# Sheet1.net
KiCad netlist of a schematic drawn in Altium Designer
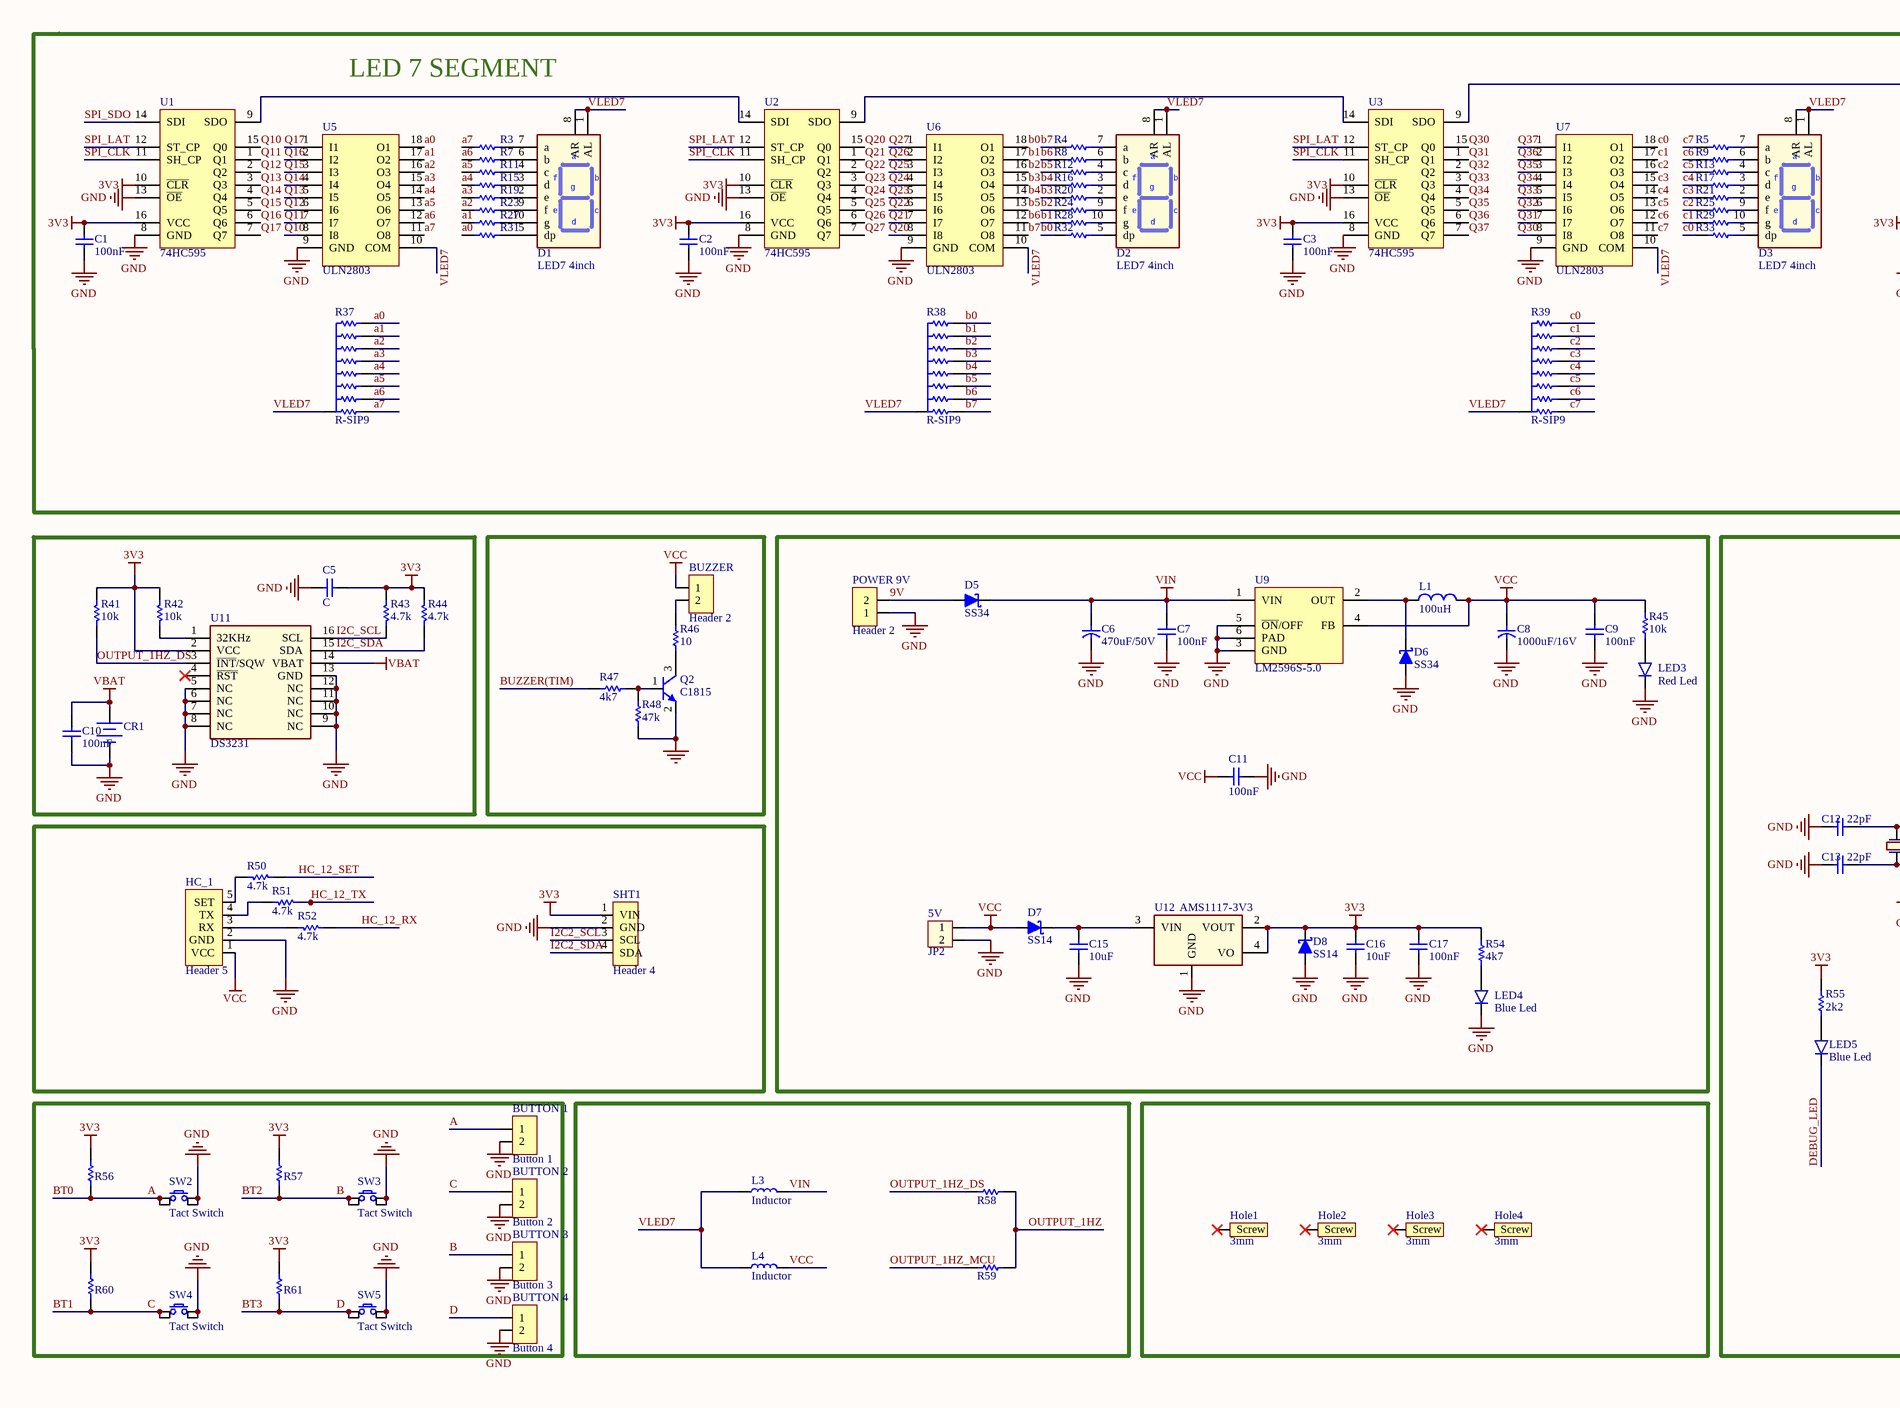
[diagram p0: Sheet1.SchDoc, left]
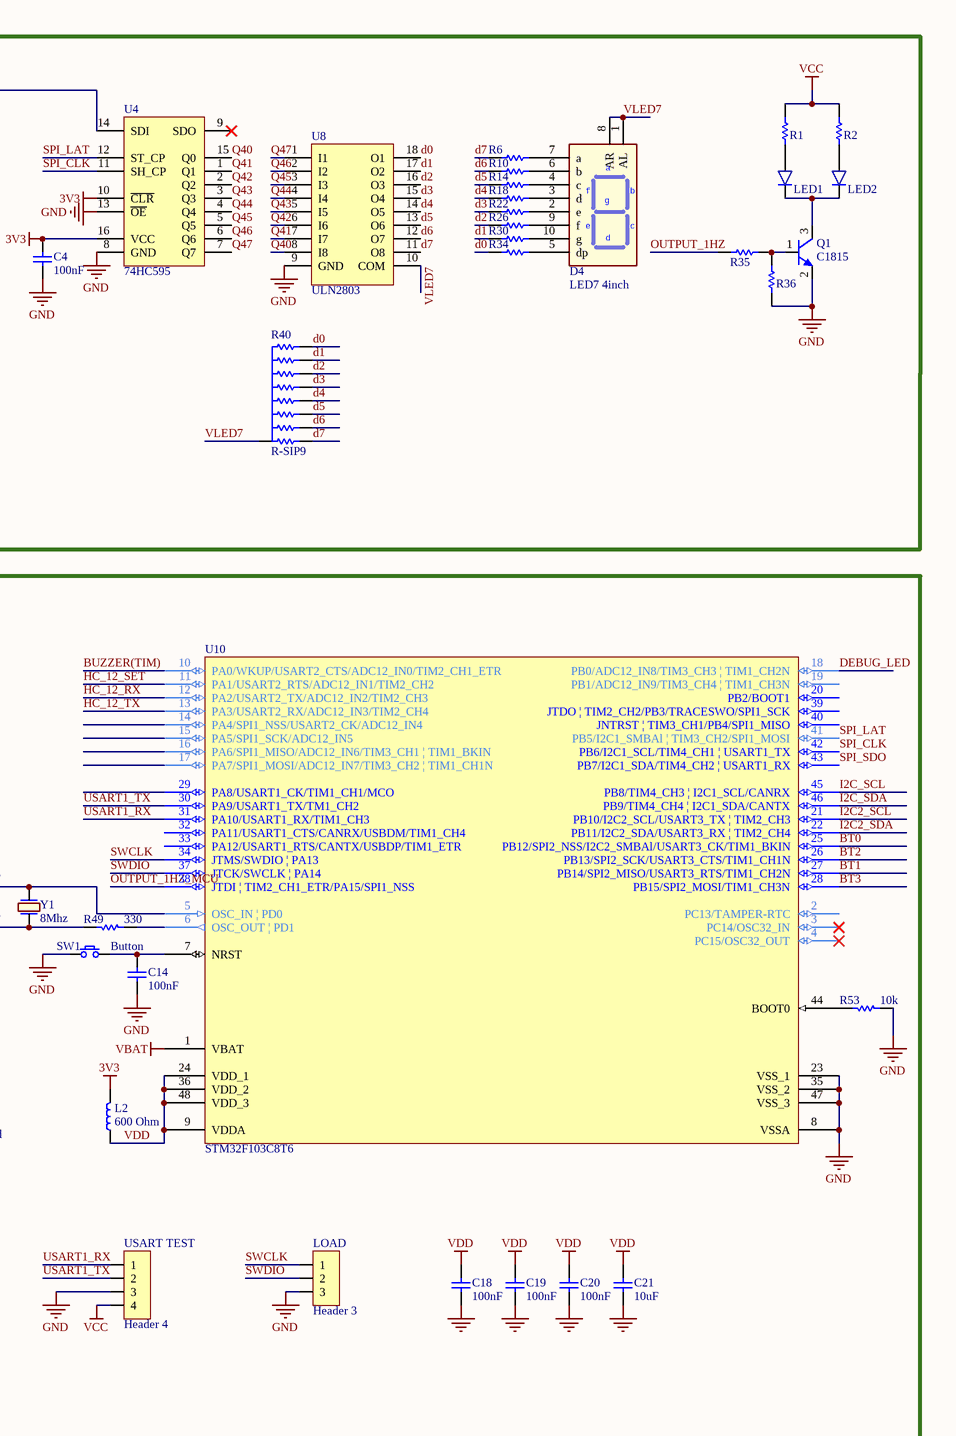
[diagram p1: Sheet1.SchDoc, right]

(export (version "E")
  (design (tool "Eeschema 10.0.6"))
  (components
    (comp (ref "5V")
      (value "JP2")
      (footprint "CON Header 2")
      (description "Connector 2")
      (libsource (lib "BKIT4U_LIB") (part "Con2"))
    )
    (comp (ref "BUTTON 1")
      (value "Button 1")
      (footprint "CON Header 2")
      (description "Header, 2-Pin")
      (fields (field (name "PUBLISHER") "Altium Limited"))
      (libsource (lib "BKIT4U_LIB") (part "Header 2"))
    )
    (comp (ref "BUTTON 2")
      (value "Button 2")
      (footprint "CON Header 2")
      (description "Header, 2-Pin")
      (fields (field (name "PUBLISHER") "Altium Limited"))
      (libsource (lib "BKIT4U_LIB") (part "Header 2"))
    )
    (comp (ref "BUTTON 3")
      (value "Button 3")
      (footprint "CON Header 2")
      (description "Header, 2-Pin")
      (fields (field (name "PUBLISHER") "Altium Limited"))
      (libsource (lib "BKIT4U_LIB") (part "Header 2"))
    )
    (comp (ref "BUTTON 4")
      (value "Button 4")
      (footprint "CON Header 2")
      (description "Header, 2-Pin")
      (fields (field (name "PUBLISHER") "Altium Limited"))
      (libsource (lib "BKIT4U_LIB") (part "Header 2"))
    )
    (comp (ref "BUZZER")
      (value "Header 2")
      (footprint "CON Header 2")
      (description "Header, 2-Pin")
      (fields (field (name "PUBLISHER") "Altium Limited"))
      (libsource (lib "BKIT4U_LIB") (part "Header 2"))
    )
    (comp (ref "C1")
      (value "100nF")
      (footprint "C 0805 (2012)")
      (description "Capacitor non-pol")
      (libsource (lib "BKIT4U_LIB") (part "Capacitor NP"))
    )
    (comp (ref "C2")
      (value "100nF")
      (footprint "C 0805 (2012)")
      (description "Capacitor non-pol")
      (libsource (lib "BKIT4U_LIB") (part "Capacitor NP"))
    )
    (comp (ref "C3")
      (value "100nF")
      (footprint "C 0805 (2012)")
      (description "Capacitor non-pol")
      (libsource (lib "BKIT4U_LIB") (part "Capacitor NP"))
    )
    (comp (ref "C4")
      (value "100nF")
      (footprint "C 0805 (2012)")
      (description "Capacitor non-pol")
      (libsource (lib "BKIT4U_LIB") (part "Capacitor NP"))
    )
    (comp (ref "C5")
      (value "C")
      (footprint "C 0805 (2012)")
      (description "Capacitor non-pol")
      (libsource (lib "BKIT4U_LIB") (part "Capacitor NP"))
    )
    (comp (ref "C6")
      (value "470uF/50V")
      (footprint "CR/D.10.0x16.0/P.5.0")
      (description "Capacitor pol")
      (libsource (lib "BKIT4U_LIB") (part "Capacitor"))
    )
    (comp (ref "C7")
      (value "100nF")
      (footprint "C 0805 (2012)")
      (description "Capacitor non-pol")
      (libsource (lib "BKIT4U_LIB") (part "Capacitor NP"))
    )
    (comp (ref "C8")
      (value "1000uF/16V")
      (footprint "CR/D.10.0x12.5/P.5.0")
      (description "Capacitor pol")
      (libsource (lib "BKIT4U_LIB") (part "Capacitor"))
    )
    (comp (ref "C9")
      (value "100nF")
      (footprint "C 0805 (2012)")
      (description "Capacitor non-pol")
      (libsource (lib "BKIT4U_LIB") (part "Capacitor NP"))
    )
    (comp (ref "C10")
      (value "100nF")
      (footprint "C 0805 (2012)")
      (description "Capacitor non-pol")
      (libsource (lib "BKIT4U_LIB") (part "Capacitor NP"))
    )
    (comp (ref "C11")
      (value "100nF")
      (footprint "C 0805 (2012)")
      (description "Capacitor non-pol")
      (libsource (lib "BKIT4U_LIB") (part "Capacitor NP"))
    )
    (comp (ref "C12")
      (value "22pF")
      (footprint "C 0805 (2012)")
      (description "Capacitor non-pol")
      (libsource (lib "BKIT4U_LIB") (part "Capacitor NP"))
    )
    (comp (ref "C13")
      (value "22pF")
      (footprint "C 0805 (2012)")
      (description "Capacitor non-pol")
      (libsource (lib "BKIT4U_LIB") (part "Capacitor NP"))
    )
    (comp (ref "C14")
      (value "100nF")
      (footprint "C 0805 (2012)")
      (description "Capacitor non-pol")
      (libsource (lib "BKIT4U_LIB") (part "Capacitor NP"))
    )
    (comp (ref "C15")
      (value "10uF")
      (footprint "C 0805 (2012)")
      (description "Capacitor non-pol")
      (libsource (lib "BKIT4U_LIB") (part "Capacitor NP"))
    )
    (comp (ref "C16")
      (value "10uF")
      (footprint "C 0805 (2012)")
      (description "Capacitor non-pol")
      (libsource (lib "BKIT4U_LIB") (part "Capacitor NP"))
    )
    (comp (ref "C17")
      (value "100nF")
      (footprint "C 0805 (2012)")
      (description "Capacitor non-pol")
      (libsource (lib "BKIT4U_LIB") (part "Capacitor NP"))
    )
    (comp (ref "C18")
      (value "100nF")
      (footprint "C 0805 (2012)")
      (description "Capacitor non-pol")
      (libsource (lib "BKIT4U_LIB") (part "Capacitor NP"))
    )
    (comp (ref "C19")
      (value "100nF")
      (footprint "C 0805 (2012)")
      (description "Capacitor non-pol")
      (libsource (lib "BKIT4U_LIB") (part "Capacitor NP"))
    )
    (comp (ref "C20")
      (value "100nF")
      (footprint "C 0805 (2012)")
      (description "Capacitor non-pol")
      (libsource (lib "BKIT4U_LIB") (part "Capacitor NP"))
    )
    (comp (ref "C21")
      (value "10uF")
      (footprint "C 0805 (2012)")
      (description "Capacitor non-pol")
      (libsource (lib "BKIT4U_LIB") (part "Capacitor NP"))
    )
    (comp (ref "CR1") (value "~") (footprint "CON CR1220") (libsource (lib "BKIT4U_LIB") (part "Battery")))
    (comp (ref "D1")
      (value "LED7 4inch")
      (footprint "LED7 4444")
      (libsource (lib "BKIT4U_LIB") (part "LED7 4inch"))
    )
    (comp (ref "D2")
      (value "LED7 4inch")
      (footprint "LED7 4444")
      (libsource (lib "BKIT4U_LIB") (part "LED7 4inch"))
    )
    (comp (ref "D3")
      (value "LED7 4inch")
      (footprint "LED7 4444")
      (libsource (lib "BKIT4U_LIB") (part "LED7 4inch"))
    )
    (comp (ref "D4")
      (value "LED7 4inch")
      (footprint "LED7 4444")
      (libsource (lib "BKIT4U_LIB") (part "LED7 4inch"))
    )
    (comp (ref "D5")
      (value "SS34")
      (footprint "DO-214AC (SMA)")
      (description "Schottky Diode")
      (fields (field (name "PUBLISHER") "Altium Limited"))
      (libsource (lib "BKIT4U_LIB") (part "Diode Schottky"))
    )
    (comp (ref "D6")
      (value "SS34")
      (footprint "DO-214AC (SMA)")
      (description "Schottky Diode")
      (fields (field (name "PUBLISHER") "Altium Limited"))
      (libsource (lib "BKIT4U_LIB") (part "Diode Schottky"))
    )
    (comp (ref "D7")
      (value "SS14")
      (footprint "DO-214AC (SMA)")
      (description "Schottky Diode")
      (fields (field (name "PUBLISHER") "Altium Limited"))
      (libsource (lib "BKIT4U_LIB") (part "Diode Schottky"))
    )
    (comp (ref "D8")
      (value "SS14")
      (footprint "DO-214AC (SMA)")
      (description "Schottky Diode")
      (fields (field (name "PUBLISHER") "Altium Limited"))
      (libsource (lib "BKIT4U_LIB") (part "Diode Schottky"))
    )
    (comp (ref "HC_1")
      (value "Header 5")
      (footprint "HC_12")
      (description "Header, 5-Pin")
      (fields (field (name "PUBLISHER") "Altium Limited"))
      (libsource (lib "BKIT4U_LIB") (part "HC_12"))
    )
    (comp (ref "Hole1") (value "3mm") (footprint "SCREW/3M/7M") (libsource (lib "BKIT4U_LIB") (part "Screw")))
    (comp (ref "Hole2") (value "3mm") (footprint "SCREW/3M/7M") (libsource (lib "BKIT4U_LIB") (part "Screw")))
    (comp (ref "Hole3") (value "3mm") (footprint "SCREW/3M/7M") (libsource (lib "BKIT4U_LIB") (part "Screw")))
    (comp (ref "Hole4") (value "3mm") (footprint "SCREW/3M/7M") (libsource (lib "BKIT4U_LIB") (part "Screw")))
    (comp (ref "L1")
      (value "100uH")
      (footprint "Inductor SMD 12x12x8")
      (description "Inductor")
      (libsource (lib "syhaunguyen") (part "L1"))
    )
    (comp (ref "L2")
      (value "600 Ohm")
      (footprint "Inductor SMD 0805 (2012)")
      (description "Inductor")
      (libsource (lib "BKIT4U_LIB") (part "Inductor"))
    )
    (comp (ref "L3")
      (value "Inductor")
      (footprint "Inductor SMD 7.5x7.0x5.0")
      (libsource (lib "BKIT4U_LIB") (part "Inductor"))
    )
    (comp (ref "L4")
      (value "Inductor")
      (footprint "Inductor SMD 7.5x7.0x5.0")
      (libsource (lib "BKIT4U_LIB") (part "Inductor"))
    )
    (comp (ref "LED1")
      (value "Led")
      (footprint "LED 5MM")
      (description "Typical LED")
      (libsource (lib "BKIT4U_LIB") (part "Led"))
    )
    (comp (ref "LED2")
      (value "Led")
      (footprint "LED 5MM")
      (description "Typical LED")
      (libsource (lib "BKIT4U_LIB") (part "Led"))
    )
    (comp (ref "LED3")
      (value "Red Led")
      (footprint "Led SMD 0805")
      (description "Typical LED")
      (libsource (lib "BKIT4U_LIB") (part "Led"))
    )
    (comp (ref "LED4")
      (value "Blue Led")
      (footprint "Led SMD 0805")
      (description "Typical LED")
      (libsource (lib "BKIT4U_LIB") (part "Led"))
    )
    (comp (ref "LED5")
      (value "Blue Led")
      (footprint "Led SMD 0805")
      (description "Typical LED")
      (libsource (lib "BKIT4U_LIB") (part "Led"))
    )
    (comp (ref "LOAD")
      (value "Header 3")
      (footprint "Header 3")
      (description "Header, 3-Pin")
      (libsource (lib "BKIT4U_LIB") (part "Header 3"))
    )
    (comp (ref "POWER 9V")
      (value "Header 2")
      (footprint "CON Header 2")
      (description "Header, 2-Pin")
      (fields (field (name "PUBLISHER") "Altium Limited"))
      (libsource (lib "") (part "Header 2_1"))
    )
    (comp (ref "Q1")
      (value "C1815")
      (footprint "SOT-23")
      (description "NPN Bipolar Transistor")
      (libsource (lib "BKIT4U_LIB") (part "Transistor NPN"))
    )
    (comp (ref "Q2")
      (value "C1815")
      (footprint "SOT-23")
      (description "NPN Bipolar Transistor")
      (libsource (lib "BKIT4U_LIB") (part "Transistor NPN"))
    )
    (comp (ref "R1")
      (value "100Ohm")
      (footprint "R 0805 (2012)")
      (description "Resistor")
      (fields (field (name "PUBLISHER") "Altium Limited"))
      (libsource (lib "BKIT4U_LIB") (part "Resistor"))
    )
    (comp (ref "R2")
      (value "100Ohm")
      (footprint "R 0805 (2012)")
      (description "Resistor")
      (fields (field (name "PUBLISHER") "Altium Limited"))
      (libsource (lib "BKIT4U_LIB") (part "Resistor"))
    )
    (comp (ref "R3")
      (value "100Ohm")
      (footprint "R 0805 (2012)")
      (description "Resistor")
      (fields (field (name "PUBLISHER") "Altium Limited"))
      (libsource (lib "BKIT4U_LIB") (part "Resistor"))
    )
    (comp (ref "R4")
      (value "100Ohm")
      (footprint "R 0805 (2012)")
      (description "Resistor")
      (fields (field (name "PUBLISHER") "Altium Limited"))
      (libsource (lib "BKIT4U_LIB") (part "Resistor"))
    )
    (comp (ref "R5")
      (value "100Ohm")
      (footprint "R 0805 (2012)")
      (description "Resistor")
      (fields (field (name "PUBLISHER") "Altium Limited"))
      (libsource (lib "BKIT4U_LIB") (part "Resistor"))
    )
    (comp (ref "R6")
      (value "100Ohm")
      (footprint "R 0805 (2012)")
      (description "Resistor")
      (fields (field (name "PUBLISHER") "Altium Limited"))
      (libsource (lib "BKIT4U_LIB") (part "Resistor"))
    )
    (comp (ref "R7")
      (value "100Ohm")
      (footprint "R 0805 (2012)")
      (description "Resistor")
      (fields (field (name "PUBLISHER") "Altium Limited"))
      (libsource (lib "BKIT4U_LIB") (part "Resistor"))
    )
    (comp (ref "R8")
      (value "100Ohm")
      (footprint "R 0805 (2012)")
      (description "Resistor")
      (fields (field (name "PUBLISHER") "Altium Limited"))
      (libsource (lib "BKIT4U_LIB") (part "Resistor"))
    )
    (comp (ref "R9")
      (value "100Ohm")
      (footprint "R 0805 (2012)")
      (description "Resistor")
      (fields (field (name "PUBLISHER") "Altium Limited"))
      (libsource (lib "BKIT4U_LIB") (part "Resistor"))
    )
    (comp (ref "R10")
      (value "100Ohm")
      (footprint "R 0805 (2012)")
      (description "Resistor")
      (fields (field (name "PUBLISHER") "Altium Limited"))
      (libsource (lib "BKIT4U_LIB") (part "Resistor"))
    )
    (comp (ref "R11")
      (value "100Ohm")
      (footprint "R 0805 (2012)")
      (description "Resistor")
      (fields (field (name "PUBLISHER") "Altium Limited"))
      (libsource (lib "BKIT4U_LIB") (part "Resistor"))
    )
    (comp (ref "R12")
      (value "100Ohm")
      (footprint "R 0805 (2012)")
      (description "Resistor")
      (fields (field (name "PUBLISHER") "Altium Limited"))
      (libsource (lib "BKIT4U_LIB") (part "Resistor"))
    )
    (comp (ref "R13")
      (value "100Ohm")
      (footprint "R 0805 (2012)")
      (description "Resistor")
      (fields (field (name "PUBLISHER") "Altium Limited"))
      (libsource (lib "BKIT4U_LIB") (part "Resistor"))
    )
    (comp (ref "R14")
      (value "100Ohm")
      (footprint "R 0805 (2012)")
      (description "Resistor")
      (fields (field (name "PUBLISHER") "Altium Limited"))
      (libsource (lib "BKIT4U_LIB") (part "Resistor"))
    )
    (comp (ref "R15")
      (value "100Ohm")
      (footprint "R 0805 (2012)")
      (description "Resistor")
      (fields (field (name "PUBLISHER") "Altium Limited"))
      (libsource (lib "BKIT4U_LIB") (part "Resistor"))
    )
    (comp (ref "R16")
      (value "100Ohm")
      (footprint "R 0805 (2012)")
      (description "Resistor")
      (fields (field (name "PUBLISHER") "Altium Limited"))
      (libsource (lib "BKIT4U_LIB") (part "Resistor"))
    )
    (comp (ref "R17")
      (value "100Ohm")
      (footprint "R 0805 (2012)")
      (description "Resistor")
      (fields (field (name "PUBLISHER") "Altium Limited"))
      (libsource (lib "BKIT4U_LIB") (part "Resistor"))
    )
    (comp (ref "R18")
      (value "100Ohm")
      (footprint "R 0805 (2012)")
      (description "Resistor")
      (fields (field (name "PUBLISHER") "Altium Limited"))
      (libsource (lib "BKIT4U_LIB") (part "Resistor"))
    )
    (comp (ref "R19")
      (value "100Ohm")
      (footprint "R 0805 (2012)")
      (description "Resistor")
      (fields (field (name "PUBLISHER") "Altium Limited"))
      (libsource (lib "BKIT4U_LIB") (part "Resistor"))
    )
    (comp (ref "R20")
      (value "100Ohm")
      (footprint "R 0805 (2012)")
      (description "Resistor")
      (fields (field (name "PUBLISHER") "Altium Limited"))
      (libsource (lib "BKIT4U_LIB") (part "Resistor"))
    )
    (comp (ref "R21")
      (value "100Ohm")
      (footprint "R 0805 (2012)")
      (description "Resistor")
      (fields (field (name "PUBLISHER") "Altium Limited"))
      (libsource (lib "BKIT4U_LIB") (part "Resistor"))
    )
    (comp (ref "R22")
      (value "100Ohm")
      (footprint "R 0805 (2012)")
      (description "Resistor")
      (fields (field (name "PUBLISHER") "Altium Limited"))
      (libsource (lib "BKIT4U_LIB") (part "Resistor"))
    )
    (comp (ref "R23")
      (value "100Ohm")
      (footprint "R 0805 (2012)")
      (description "Resistor")
      (fields (field (name "PUBLISHER") "Altium Limited"))
      (libsource (lib "BKIT4U_LIB") (part "Resistor"))
    )
    (comp (ref "R24")
      (value "100Ohm")
      (footprint "R 0805 (2012)")
      (description "Resistor")
      (fields (field (name "PUBLISHER") "Altium Limited"))
      (libsource (lib "BKIT4U_LIB") (part "Resistor"))
    )
    (comp (ref "R25")
      (value "100Ohm")
      (footprint "R 0805 (2012)")
      (description "Resistor")
      (fields (field (name "PUBLISHER") "Altium Limited"))
      (libsource (lib "BKIT4U_LIB") (part "Resistor"))
    )
    (comp (ref "R26")
      (value "100Ohm")
      (footprint "R 0805 (2012)")
      (description "Resistor")
      (fields (field (name "PUBLISHER") "Altium Limited"))
      (libsource (lib "BKIT4U_LIB") (part "Resistor"))
    )
    (comp (ref "R27")
      (value "100Ohm")
      (footprint "R 0805 (2012)")
      (description "Resistor")
      (fields (field (name "PUBLISHER") "Altium Limited"))
      (libsource (lib "BKIT4U_LIB") (part "Resistor"))
    )
    (comp (ref "R28")
      (value "100Ohm")
      (footprint "R 0805 (2012)")
      (description "Resistor")
      (fields (field (name "PUBLISHER") "Altium Limited"))
      (libsource (lib "BKIT4U_LIB") (part "Resistor"))
    )
    (comp (ref "R29")
      (value "100Ohm")
      (footprint "R 0805 (2012)")
      (description "Resistor")
      (fields (field (name "PUBLISHER") "Altium Limited"))
      (libsource (lib "BKIT4U_LIB") (part "Resistor"))
    )
    (comp (ref "R30")
      (value "100Ohm")
      (footprint "R 0805 (2012)")
      (description "Resistor")
      (fields (field (name "PUBLISHER") "Altium Limited"))
      (libsource (lib "BKIT4U_LIB") (part "Resistor"))
    )
    (comp (ref "R31")
      (value "100Ohm")
      (footprint "R 0805 (2012)")
      (description "Resistor")
      (fields (field (name "PUBLISHER") "Altium Limited"))
      (libsource (lib "BKIT4U_LIB") (part "Resistor"))
    )
    (comp (ref "R32")
      (value "100Ohm")
      (footprint "R 0805 (2012)")
      (description "Resistor")
      (fields (field (name "PUBLISHER") "Altium Limited"))
      (libsource (lib "BKIT4U_LIB") (part "Resistor"))
    )
    (comp (ref "R33")
      (value "100Ohm")
      (footprint "R 0805 (2012)")
      (description "Resistor")
      (fields (field (name "PUBLISHER") "Altium Limited"))
      (libsource (lib "BKIT4U_LIB") (part "Resistor"))
    )
    (comp (ref "R34")
      (value "100Ohm")
      (footprint "R 0805 (2012)")
      (description "Resistor")
      (fields (field (name "PUBLISHER") "Altium Limited"))
      (libsource (lib "BKIT4U_LIB") (part "Resistor"))
    )
    (comp (ref "R35")
      (value "100Ohm")
      (footprint "R 0805 (2012)")
      (description "Resistor")
      (fields (field (name "PUBLISHER") "Altium Limited"))
      (libsource (lib "BKIT4U_LIB") (part "Resistor"))
    )
    (comp (ref "R36")
      (value "100Ohm")
      (footprint "R 0805 (2012)")
      (description "Resistor")
      (fields (field (name "PUBLISHER") "Altium Limited"))
      (libsource (lib "BKIT4U_LIB") (part "Resistor"))
    )
    (comp (ref "R37")
      (value "R-SIP9")
      (footprint "R SIP9")
      (description "Resistor")
      (fields (field (name "PUBLISHER") "Altium Limited"))
      (libsource (lib "BKIT4U_LIB") (part "Resistor Sip9"))
    )
    (comp (ref "R38")
      (value "R-SIP9")
      (footprint "R SIP9")
      (description "Resistor")
      (fields (field (name "PUBLISHER") "Altium Limited"))
      (libsource (lib "BKIT4U_LIB") (part "Resistor Sip9"))
    )
    (comp (ref "R39")
      (value "R-SIP9")
      (footprint "R SIP9")
      (description "Resistor")
      (fields (field (name "PUBLISHER") "Altium Limited"))
      (libsource (lib "BKIT4U_LIB") (part "Resistor Sip9"))
    )
    (comp (ref "R40")
      (value "R-SIP9")
      (footprint "R SIP9")
      (description "Resistor")
      (fields (field (name "PUBLISHER") "Altium Limited"))
      (libsource (lib "BKIT4U_LIB") (part "Resistor Sip9"))
    )
    (comp (ref "R41")
      (value "10k")
      (footprint "R 0805 (2012)")
      (description "Resistor")
      (fields (field (name "PUBLISHER") "Altium Limited"))
      (libsource (lib "BKIT4U_LIB") (part "Resistor"))
    )
    (comp (ref "R42")
      (value "10k")
      (footprint "R 0805 (2012)")
      (description "Resistor")
      (fields (field (name "PUBLISHER") "Altium Limited"))
      (libsource (lib "BKIT4U_LIB") (part "Resistor"))
    )
    (comp (ref "R43")
      (value "4.7k")
      (footprint "R 0805 (2012)")
      (description "Resistor")
      (fields (field (name "PUBLISHER") "Altium Limited"))
      (libsource (lib "BKIT4U_LIB") (part "Resistor"))
    )
    (comp (ref "R44")
      (value "4.7k")
      (footprint "R 0805 (2012)")
      (description "Resistor")
      (fields (field (name "PUBLISHER") "Altium Limited"))
      (libsource (lib "BKIT4U_LIB") (part "Resistor"))
    )
    (comp (ref "R45")
      (value "10k")
      (footprint "R 0805 (2012)")
      (description "Resistor")
      (fields (field (name "PUBLISHER") "Altium Limited"))
      (libsource (lib "BKIT4U_LIB") (part "Resistor"))
    )
    (comp (ref "R46")
      (value "10")
      (footprint "R 0805 (2012)")
      (description "Resistor")
      (fields (field (name "PUBLISHER") "Altium Limited"))
      (libsource (lib "BKIT4U_LIB") (part "Resistor"))
    )
    (comp (ref "R47")
      (value "4k7")
      (footprint "R 0805 (2012)")
      (description "Resistor")
      (fields (field (name "PUBLISHER") "Altium Limited"))
      (libsource (lib "BKIT4U_LIB") (part "Resistor"))
    )
    (comp (ref "R48")
      (value "47k")
      (footprint "R 0805 (2012)")
      (description "Resistor")
      (fields (field (name "PUBLISHER") "Altium Limited"))
      (libsource (lib "BKIT4U_LIB") (part "Resistor"))
    )
    (comp (ref "R49")
      (value "330")
      (footprint "R 0805 (2012)")
      (description "Resistor")
      (fields (field (name "PUBLISHER") "Altium Limited"))
      (libsource (lib "BKIT4U_LIB") (part "Resistor"))
    )
    (comp (ref "R50")
      (value "4.7k")
      (footprint "R 0805 (2012)")
      (description "Resistor")
      (fields (field (name "PUBLISHER") "Altium Limited"))
      (libsource (lib "BKIT4U_LIB") (part "Resistor"))
    )
    (comp (ref "R51")
      (value "4.7k")
      (footprint "R 0805 (2012)")
      (description "Resistor")
      (fields (field (name "PUBLISHER") "Altium Limited"))
      (libsource (lib "BKIT4U_LIB") (part "Resistor"))
    )
    (comp (ref "R52")
      (value "4.7k")
      (footprint "R 0805 (2012)")
      (description "Resistor")
      (fields (field (name "PUBLISHER") "Altium Limited"))
      (libsource (lib "BKIT4U_LIB") (part "Resistor"))
    )
    (comp (ref "R53")
      (value "10k")
      (footprint "R 0805 (2012)")
      (description "Resistor")
      (fields (field (name "PUBLISHER") "Altium Limited"))
      (libsource (lib "BKIT4U_LIB") (part "Resistor"))
    )
    (comp (ref "R54")
      (value "4k7")
      (footprint "R 0805 (2012)")
      (description "Resistor")
      (fields (field (name "PUBLISHER") "Altium Limited"))
      (libsource (lib "BKIT4U_LIB") (part "Resistor"))
    )
    (comp (ref "R55")
      (value "2k2")
      (footprint "R 0805 (2012)")
      (description "Resistor")
      (fields (field (name "PUBLISHER") "Altium Limited"))
      (libsource (lib "BKIT4U_LIB") (part "Resistor"))
    )
    (comp (ref "R56")
      (value "100Ohm")
      (footprint "R 0805 (2012)")
      (description "Resistor")
      (fields (field (name "PUBLISHER") "Altium Limited"))
      (libsource (lib "BKIT4U_LIB") (part "Resistor"))
    )
    (comp (ref "R57")
      (value "100Ohm")
      (footprint "R 0805 (2012)")
      (description "Resistor")
      (fields (field (name "PUBLISHER") "Altium Limited"))
      (libsource (lib "BKIT4U_LIB") (part "Resistor"))
    )
    (comp (ref "R58")
      (value "100Ohm")
      (footprint "R 0805 (2012)")
      (description "Resistor")
      (fields (field (name "PUBLISHER") "Altium Limited"))
      (libsource (lib "BKIT4U_LIB") (part "Resistor"))
    )
    (comp (ref "R59")
      (value "100Ohm")
      (footprint "R 0805 (2012)")
      (description "Resistor")
      (fields (field (name "PUBLISHER") "Altium Limited"))
      (libsource (lib "BKIT4U_LIB") (part "Resistor"))
    )
    (comp (ref "R60")
      (value "100Ohm")
      (footprint "R 0805 (2012)")
      (description "Resistor")
      (fields (field (name "PUBLISHER") "Altium Limited"))
      (libsource (lib "BKIT4U_LIB") (part "Resistor"))
    )
    (comp (ref "R61")
      (value "100Ohm")
      (footprint "R 0805 (2012)")
      (description "Resistor")
      (fields (field (name "PUBLISHER") "Altium Limited"))
      (libsource (lib "BKIT4U_LIB") (part "Resistor"))
    )
    (comp (ref "SHT1")
      (value "Header 4")
      (footprint "CON Header 4")
      (description "Header, 4-Pin")
      (libsource (lib "BKIT4U_LIB") (part "Header 4"))
    )
    (comp (ref "SW1")
      (value "Button")
      (footprint "SW/2/SMD")
      (description "Tact switch 2 pin")
      (libsource (lib "BKIT4U_LIB") (part "SW SPST"))
    )
    (comp (ref "SW2")
      (value "Tact Switch")
      (footprint "SW/4/SMD/SMALL")
      (description "Tact switch 4 pin")
      (libsource (lib "BKIT4U_LIB") (part "SW SPST-4"))
    )
    (comp (ref "SW3")
      (value "Tact Switch")
      (footprint "SW/4/SMD/SMALL")
      (description "Tact switch 4 pin")
      (libsource (lib "BKIT4U_LIB") (part "SW SPST-4"))
    )
    (comp (ref "SW4")
      (value "Tact Switch")
      (footprint "SW/4/SMD/SMALL")
      (description "Tact switch 4 pin")
      (libsource (lib "BKIT4U_LIB") (part "SW SPST-4"))
    )
    (comp (ref "SW5")
      (value "Tact Switch")
      (footprint "SW/4/SMD/SMALL")
      (description "Tact switch 4 pin")
      (libsource (lib "BKIT4U_LIB") (part "SW SPST-4"))
    )
    (comp (ref "U1")
      (value "74HC595")
      (footprint "SOIC-16")
      (description "8-bit serial-in, serial or parallel-out  shift register with output latches;  3-state")
      (libsource (lib "BKIT4U_LIB") (part "74HC595"))
    )
    (comp (ref "U2")
      (value "74HC595")
      (footprint "SOIC-16")
      (description "8-bit serial-in, serial or parallel-out  shift register with output latches;  3-state")
      (libsource (lib "BKIT4U_LIB") (part "74HC595"))
    )
    (comp (ref "U3")
      (value "74HC595")
      (footprint "SOIC-16")
      (description "8-bit serial-in, serial or parallel-out  shift register with output latches;  3-state")
      (libsource (lib "BKIT4U_LIB") (part "74HC595"))
    )
    (comp (ref "U4")
      (value "74HC595")
      (footprint "SOIC-16")
      (description "8-bit serial-in, serial or parallel-out  shift register with output latches;  3-state")
      (libsource (lib "BKIT4U_LIB") (part "74HC595"))
    )
    (comp (ref "U5")
      (value "ULN2803")
      (footprint "SOIC-18")
      (description "High-voltage, high-current Darlington transistor arrays")
      (libsource (lib "BKIT4U_LIB") (part "ULN2803"))
    )
    (comp (ref "U6")
      (value "ULN2803")
      (footprint "SOIC-18")
      (description "High-voltage, high-current Darlington transistor arrays")
      (libsource (lib "BKIT4U_LIB") (part "ULN2803"))
    )
    (comp (ref "U7")
      (value "ULN2803")
      (footprint "SOIC-18")
      (description "High-voltage, high-current Darlington transistor arrays")
      (libsource (lib "BKIT4U_LIB") (part "ULN2803"))
    )
    (comp (ref "U8")
      (value "ULN2803")
      (footprint "SOIC-18")
      (description "High-voltage, high-current Darlington transistor arrays")
      (libsource (lib "BKIT4U_LIB") (part "ULN2803"))
    )
    (comp (ref "U9")
      (value "LM2596S-5.0")
      (footprint "TO-263-5")
      (description "SIMPLE SWITCHER® 3A Step-Down Voltage Regulator")
      (libsource (lib "BKIT4U_LIB") (part "LM2576/96"))
    )
    (comp (ref "U10")
      (value "STM32F103C8T6")
      (footprint "LQFP48_N")
      (description "STM32 ARM-based 32-bit MCU with 64 Kbytes Flash, 48-pin LQFP, Industrial Temperature")
      (fields (field (name "PUBLISHER") "Altium Limited"))
      (libsource (lib "BKIT4U_LIB") (part "STM32F103C8T6"))
    )
    (comp (ref "U11")
      (value "DS3231")
      (footprint "SOIC-16-WIDE")
      (libsource (lib "BKIT4U_LIB") (part "DS3231"))
    )
    (comp (ref "U12")
      (value "AMS1117-3V3")
      (footprint "SOT-223")
      (description "1A LDO Voltage Regulator, ADJ or fixed 1.5/1.8/2.5/2.85/3.3/5V")
      (libsource (lib "BKIT4U_LIB") (part "AMS1117"))
    )
    (comp (ref "USART TEST")
      (value "Header 4")
      (footprint "CON Header 4")
      (description "Header, 4-Pin")
      (libsource (lib "") (part "Header 4_1"))
    )
    (comp (ref "Y1")
      (value "8Mhz")
      (footprint "Crystal HC49US SMD")
      (libsource (lib "BKIT4U_LIB") (part "Crystal"))
    )
  )
  (nets
    (net (code "1") (name "/9V") (class "Default")
      (node (ref "D5") (pin "1") (pinfunction "A_1") (pintype "passive"))
      (node (ref "POWER 9V") (pin "2") (pinfunction "2_2") (pintype "passive"))
    )
    (net (code "2") (name "/A") (class "Default")
      (node (ref "BUTTON 1") (pin "1") (pinfunction "1_1") (pintype "passive"))
      (node (ref "R56") (pin "1") (pinfunction "1_1") (pintype "passive"))
      (node (ref "SW2") (pin "1") (pinfunction "1_1") (pintype "passive"))
      (node (ref "SW2") (pin "4") (pinfunction "2_4") (pintype "passive"))
      (node (ref "U10") (pin "25") (pinfunction "PB12/SPI2_NSS/I2C2_SMBAl/USART3_CK/TIM1_BKIN_25") (pintype "bidirectional"))
    )
    (net (code "3") (name "/B") (class "Default")
      (node (ref "BUTTON 3") (pin "1") (pinfunction "1_1") (pintype "passive"))
      (node (ref "R57") (pin "1") (pinfunction "1_1") (pintype "passive"))
      (node (ref "SW3") (pin "1") (pinfunction "1_1") (pintype "passive"))
      (node (ref "SW3") (pin "4") (pinfunction "2_4") (pintype "passive"))
      (node (ref "U10") (pin "26") (pinfunction "PB13/SPI2_SCK/USART3_CTS/TIM1_CH1N_26") (pintype "bidirectional"))
    )
    (net (code "4") (name "/BT1") (class "Default")
      (node (ref "BUTTON 2") (pin "1") (pinfunction "1_1") (pintype "passive"))
      (node (ref "R60") (pin "1") (pinfunction "1_1") (pintype "passive"))
      (node (ref "SW4") (pin "1") (pinfunction "1_1") (pintype "passive"))
      (node (ref "SW4") (pin "4") (pinfunction "2_4") (pintype "passive"))
      (node (ref "U10") (pin "27") (pinfunction "PB14/SPI2_MISO/USART3_RTS/TIM1_CH2N_27") (pintype "bidirectional"))
    )
    (net (code "5") (name "/BT3") (class "Default")
      (node (ref "BUTTON 4") (pin "1") (pinfunction "1_1") (pintype "passive"))
      (node (ref "R61") (pin "1") (pinfunction "1_1") (pintype "passive"))
      (node (ref "SW5") (pin "1") (pinfunction "1_1") (pintype "passive"))
      (node (ref "SW5") (pin "4") (pinfunction "2_4") (pintype "passive"))
      (node (ref "U10") (pin "28") (pinfunction "PB15/SPI2_MOSI/TIM1_CH3N_28") (pintype "bidirectional"))
    )
    (net (code "6") (name "/BUZZER(TIM)") (class "Default")
      (node (ref "R47") (pin "2") (pinfunction "2_2") (pintype "passive"))
      (node (ref "U10") (pin "10") (pinfunction "PA0/WKUP/USART2_CTS/ADC12_IN0/TIM2_CH1_ETR_10") (pintype "bidirectional"))
    )
    (net (code "7") (name "/DEBUG_LED") (class "Default")
      (node (ref "LED5") (pin "2") (pinfunction "K_2") (pintype "passive"))
      (node (ref "U10") (pin "18") (pinfunction "PB0/ADC12_IN8/TIM3_CH3_¦_TIM1_CH2N_18") (pintype "bidirectional"))
    )
    (net (code "8") (name "/HC_12_RX") (class "Default")
      (node (ref "R52") (pin "2") (pinfunction "2_2") (pintype "passive"))
      (node (ref "U10") (pin "12") (pinfunction "PA2/USART2_TX/ADC12_IN2/TIM2_CH3_12") (pintype "bidirectional"))
    )
    (net (code "9") (name "/HC_12_SET") (class "Default")
      (node (ref "R50") (pin "2") (pinfunction "2_2") (pintype "passive"))
      (node (ref "U10") (pin "11") (pinfunction "PA1/USART2_RTS/ADC12_IN1/TIM2_CH2_11") (pintype "bidirectional"))
    )
    (net (code "10") (name "/HC_12_TX") (class "Default")
      (node (ref "R51") (pin "2") (pinfunction "2_2") (pintype "passive"))
      (node (ref "U10") (pin "13") (pinfunction "PA3/USART2_RX/ADC12_IN3/TIM2_CH4_13") (pintype "bidirectional"))
    )
    (net (code "11") (name "/I2C2_SCL") (class "Default")
      (node (ref "SHT1") (pin "3") (pinfunction "SCL_3") (pintype "passive"))
      (node (ref "U10") (pin "21") (pinfunction "PB10/I2C2_SCL/USART3_TX_¦_TIM2_CH3_21") (pintype "bidirectional"))
    )
    (net (code "12") (name "/I2C2_SDA") (class "Default")
      (node (ref "SHT1") (pin "4") (pinfunction "SDA_4") (pintype "passive"))
      (node (ref "U10") (pin "22") (pinfunction "PB11/I2C2_SDA/USART3_RX_¦_TIM2_CH4_22") (pintype "bidirectional"))
    )
    (net (code "13") (name "/I2C_SCL") (class "Default")
      (node (ref "R43") (pin "2") (pinfunction "2_2") (pintype "passive"))
      (node (ref "U10") (pin "45") (pinfunction "PB8/TIM4_CH3_¦_I2C1_SCL/CANRX_45") (pintype "bidirectional"))
      (node (ref "U11") (pin "16") (pinfunction "SCL_16") (pintype "passive"))
    )
    (net (code "14") (name "/I2C_SDA") (class "Default")
      (node (ref "R44") (pin "2") (pinfunction "2_2") (pintype "passive"))
      (node (ref "U10") (pin "46") (pinfunction "PB9/TIM4_CH4_¦_I2C1_SDA/CANTX_46") (pintype "bidirectional"))
      (node (ref "U11") (pin "15") (pinfunction "SDA_15") (pintype "passive"))
    )
    (net (code "15") (name "/OUTPUT_1HZ") (class "Default")
      (node (ref "R35") (pin "1") (pinfunction "1_1") (pintype "passive"))
      (node (ref "R58") (pin "1") (pinfunction "1_1") (pintype "passive"))
      (node (ref "R59") (pin "1") (pinfunction "1_1") (pintype "passive"))
    )
    (net (code "16") (name "/OUTPUT_1HZ_DS") (class "Default")
      (node (ref "R41") (pin "2") (pinfunction "2_2") (pintype "passive"))
      (node (ref "R58") (pin "2") (pinfunction "2_2") (pintype "passive"))
      (node (ref "U11") (pin "3") (pinfunction "~{INT}/SQW_3") (pintype "passive"))
    )
    (net (code "17") (name "/OUTPUT_1HZ_MCU") (class "Default")
      (node (ref "R59") (pin "2") (pinfunction "2_2") (pintype "passive"))
      (node (ref "U10") (pin "38") (pinfunction "JTDI_¦_TIM2_CH1_ETR/PA15/SPI1_NSS_38") (pintype "bidirectional"))
    )
    (net (code "18") (name "/Q10") (class "Default")
      (node (ref "U1") (pin "15") (pinfunction "Q0_15") (pintype "passive"))
      (node (ref "U5") (pin "8") (pinfunction "I8_8") (pintype "passive"))
    )
    (net (code "19") (name "/Q11") (class "Default")
      (node (ref "U1") (pin "1") (pinfunction "Q1_1") (pintype "passive"))
      (node (ref "U5") (pin "7") (pinfunction "I7_7") (pintype "passive"))
    )
    (net (code "20") (name "/Q12") (class "Default")
      (node (ref "U1") (pin "2") (pinfunction "Q2_2") (pintype "passive"))
      (node (ref "U5") (pin "6") (pinfunction "I6_6") (pintype "passive"))
    )
    (net (code "21") (name "/Q13") (class "Default")
      (node (ref "U1") (pin "3") (pinfunction "Q3_3") (pintype "passive"))
      (node (ref "U5") (pin "5") (pinfunction "I5_5") (pintype "passive"))
    )
    (net (code "22") (name "/Q14") (class "Default")
      (node (ref "U1") (pin "4") (pinfunction "Q4_4") (pintype "passive"))
      (node (ref "U5") (pin "4") (pinfunction "I4_4") (pintype "passive"))
    )
    (net (code "23") (name "/Q15") (class "Default")
      (node (ref "U1") (pin "5") (pinfunction "Q5_5") (pintype "passive"))
      (node (ref "U5") (pin "3") (pinfunction "I3_3") (pintype "passive"))
    )
    (net (code "24") (name "/Q16") (class "Default")
      (node (ref "U1") (pin "6") (pinfunction "Q6_6") (pintype "passive"))
      (node (ref "U5") (pin "2") (pinfunction "I2_2") (pintype "passive"))
    )
    (net (code "25") (name "/Q17") (class "Default")
      (node (ref "U1") (pin "7") (pinfunction "Q7_7") (pintype "passive"))
      (node (ref "U5") (pin "1") (pinfunction "I1_1") (pintype "passive"))
    )
    (net (code "26") (name "/Q20") (class "Default")
      (node (ref "U2") (pin "15") (pinfunction "Q0_15") (pintype "passive"))
      (node (ref "U6") (pin "8") (pinfunction "I8_8") (pintype "passive"))
    )
    (net (code "27") (name "/Q21") (class "Default")
      (node (ref "U2") (pin "1") (pinfunction "Q1_1") (pintype "passive"))
      (node (ref "U6") (pin "7") (pinfunction "I7_7") (pintype "passive"))
    )
    (net (code "28") (name "/Q22") (class "Default")
      (node (ref "U2") (pin "2") (pinfunction "Q2_2") (pintype "passive"))
      (node (ref "U6") (pin "6") (pinfunction "I6_6") (pintype "passive"))
    )
    (net (code "29") (name "/Q23") (class "Default")
      (node (ref "U2") (pin "3") (pinfunction "Q3_3") (pintype "passive"))
      (node (ref "U6") (pin "5") (pinfunction "I5_5") (pintype "passive"))
    )
    (net (code "30") (name "/Q24") (class "Default")
      (node (ref "U2") (pin "4") (pinfunction "Q4_4") (pintype "passive"))
      (node (ref "U6") (pin "4") (pinfunction "I4_4") (pintype "passive"))
    )
    (net (code "31") (name "/Q25") (class "Default")
      (node (ref "U2") (pin "5") (pinfunction "Q5_5") (pintype "passive"))
      (node (ref "U6") (pin "3") (pinfunction "I3_3") (pintype "passive"))
    )
    (net (code "32") (name "/Q26") (class "Default")
      (node (ref "U2") (pin "6") (pinfunction "Q6_6") (pintype "passive"))
      (node (ref "U6") (pin "2") (pinfunction "I2_2") (pintype "passive"))
    )
    (net (code "33") (name "/Q27") (class "Default")
      (node (ref "U2") (pin "7") (pinfunction "Q7_7") (pintype "passive"))
      (node (ref "U6") (pin "1") (pinfunction "I1_1") (pintype "passive"))
    )
    (net (code "34") (name "/Q30") (class "Default")
      (node (ref "U3") (pin "15") (pinfunction "Q0_15") (pintype "passive"))
      (node (ref "U7") (pin "8") (pinfunction "I8_8") (pintype "passive"))
    )
    (net (code "35") (name "/Q31") (class "Default")
      (node (ref "U3") (pin "1") (pinfunction "Q1_1") (pintype "passive"))
      (node (ref "U7") (pin "7") (pinfunction "I7_7") (pintype "passive"))
    )
    (net (code "36") (name "/Q32") (class "Default")
      (node (ref "U3") (pin "2") (pinfunction "Q2_2") (pintype "passive"))
      (node (ref "U7") (pin "6") (pinfunction "I6_6") (pintype "passive"))
    )
    (net (code "37") (name "/Q33") (class "Default")
      (node (ref "U3") (pin "3") (pinfunction "Q3_3") (pintype "passive"))
      (node (ref "U7") (pin "5") (pinfunction "I5_5") (pintype "passive"))
    )
    (net (code "38") (name "/Q34") (class "Default")
      (node (ref "U3") (pin "4") (pinfunction "Q4_4") (pintype "passive"))
      (node (ref "U7") (pin "4") (pinfunction "I4_4") (pintype "passive"))
    )
    (net (code "39") (name "/Q35") (class "Default")
      (node (ref "U3") (pin "5") (pinfunction "Q5_5") (pintype "passive"))
      (node (ref "U7") (pin "3") (pinfunction "I3_3") (pintype "passive"))
    )
    (net (code "40") (name "/Q36") (class "Default")
      (node (ref "U3") (pin "6") (pinfunction "Q6_6") (pintype "passive"))
      (node (ref "U7") (pin "2") (pinfunction "I2_2") (pintype "passive"))
    )
    (net (code "41") (name "/Q37") (class "Default")
      (node (ref "U3") (pin "7") (pinfunction "Q7_7") (pintype "passive"))
      (node (ref "U7") (pin "1") (pinfunction "I1_1") (pintype "passive"))
    )
    (net (code "42") (name "/Q40") (class "Default")
      (node (ref "U4") (pin "15") (pinfunction "Q0_15") (pintype "passive"))
      (node (ref "U8") (pin "8") (pinfunction "I8_8") (pintype "passive"))
    )
    (net (code "43") (name "/Q41") (class "Default")
      (node (ref "U4") (pin "1") (pinfunction "Q1_1") (pintype "passive"))
      (node (ref "U8") (pin "7") (pinfunction "I7_7") (pintype "passive"))
    )
    (net (code "44") (name "/Q42") (class "Default")
      (node (ref "U4") (pin "2") (pinfunction "Q2_2") (pintype "passive"))
      (node (ref "U8") (pin "6") (pinfunction "I6_6") (pintype "passive"))
    )
    (net (code "45") (name "/Q43") (class "Default")
      (node (ref "U4") (pin "3") (pinfunction "Q3_3") (pintype "passive"))
      (node (ref "U8") (pin "5") (pinfunction "I5_5") (pintype "passive"))
    )
    (net (code "46") (name "/Q44") (class "Default")
      (node (ref "U4") (pin "4") (pinfunction "Q4_4") (pintype "passive"))
      (node (ref "U8") (pin "4") (pinfunction "I4_4") (pintype "passive"))
    )
    (net (code "47") (name "/Q45") (class "Default")
      (node (ref "U4") (pin "5") (pinfunction "Q5_5") (pintype "passive"))
      (node (ref "U8") (pin "3") (pinfunction "I3_3") (pintype "passive"))
    )
    (net (code "48") (name "/Q46") (class "Default")
      (node (ref "U4") (pin "6") (pinfunction "Q6_6") (pintype "passive"))
      (node (ref "U8") (pin "2") (pinfunction "I2_2") (pintype "passive"))
    )
    (net (code "49") (name "/Q47") (class "Default")
      (node (ref "U4") (pin "7") (pinfunction "Q7_7") (pintype "passive"))
      (node (ref "U8") (pin "1") (pinfunction "I1_1") (pintype "passive"))
    )
    (net (code "50") (name "/SPI_CLK") (class "Default")
      (node (ref "U1") (pin "11") (pinfunction "SH_CP_11") (pintype "passive"))
      (node (ref "U10") (pin "42") (pinfunction "PB6/I2C1_SCL/TIM4_CH1_¦_USART1_TX_42") (pintype "bidirectional"))
      (node (ref "U2") (pin "11") (pinfunction "SH_CP_11") (pintype "passive"))
      (node (ref "U3") (pin "11") (pinfunction "SH_CP_11") (pintype "passive"))
      (node (ref "U4") (pin "11") (pinfunction "SH_CP_11") (pintype "passive"))
    )
    (net (code "51") (name "/SPI_LAT") (class "Default")
      (node (ref "U1") (pin "12") (pinfunction "ST_CP_12") (pintype "passive"))
      (node (ref "U10") (pin "41") (pinfunction "PB5/I2C1_SMBAl_¦_TIM3_CH2/SPI1_MOSI_41") (pintype "bidirectional"))
      (node (ref "U2") (pin "12") (pinfunction "ST_CP_12") (pintype "passive"))
      (node (ref "U3") (pin "12") (pinfunction "ST_CP_12") (pintype "passive"))
      (node (ref "U4") (pin "12") (pinfunction "ST_CP_12") (pintype "passive"))
    )
    (net (code "52") (name "/SPI_SDO") (class "Default")
      (node (ref "U1") (pin "14") (pinfunction "SDI_14") (pintype "passive"))
      (node (ref "U10") (pin "43") (pinfunction "PB7/I2C1_SDA/TIM4_CH2_¦_USART1_RX_43") (pintype "bidirectional"))
    )
    (net (code "53") (name "/SWCLK") (class "Default")
      (node (ref "LOAD") (pin "1") (pinfunction "1_1") (pintype "passive"))
      (node (ref "U10") (pin "34") (pinfunction "JTMS/SWDIO_¦_PA13_34") (pintype "bidirectional"))
    )
    (net (code "54") (name "/SWDIO") (class "Default")
      (node (ref "LOAD") (pin "2") (pinfunction "2_2") (pintype "passive"))
      (node (ref "U10") (pin "37") (pinfunction "JTCK/SWCLK_¦_PA14_37") (pintype "bidirectional"))
    )
    (net (code "55") (name "/USART1_RX") (class "Default")
      (node (ref "U10") (pin "31") (pinfunction "PA10/USART1_RX/TIM1_CH3_31") (pintype "bidirectional"))
      (node (ref "USART TEST") (pin "1") (pinfunction "1_1") (pintype "passive"))
    )
    (net (code "56") (name "/USART1_TX") (class "Default")
      (node (ref "U10") (pin "30") (pinfunction "PA9/USART1_TX/TM1_CH2_30") (pintype "bidirectional"))
      (node (ref "USART TEST") (pin "2") (pinfunction "2_2") (pintype "passive"))
    )
    (net (code "57") (name "/VLED7") (class "Default")
      (node (ref "D1") (pin "1") (pinfunction "AL_1") (pintype "passive"))
      (node (ref "D1") (pin "8") (pinfunction "AR_8") (pintype "passive"))
      (node (ref "D2") (pin "1") (pinfunction "AL_1") (pintype "passive"))
      (node (ref "D2") (pin "8") (pinfunction "AR_8") (pintype "passive"))
      (node (ref "D3") (pin "1") (pinfunction "AL_1") (pintype "passive"))
      (node (ref "D3") (pin "8") (pinfunction "AR_8") (pintype "passive"))
      (node (ref "D4") (pin "1") (pinfunction "AL_1") (pintype "passive"))
      (node (ref "D4") (pin "8") (pinfunction "AR_8") (pintype "passive"))
      (node (ref "L3") (pin "1") (pinfunction "1_1") (pintype "passive"))
      (node (ref "L4") (pin "1") (pinfunction "1_1") (pintype "passive"))
      (node (ref "R37") (pin "1") (pinfunction "1_1") (pintype "passive"))
      (node (ref "R38") (pin "1") (pinfunction "1_1") (pintype "passive"))
      (node (ref "R39") (pin "1") (pinfunction "1_1") (pintype "passive"))
      (node (ref "R40") (pin "1") (pinfunction "1_1") (pintype "passive"))
      (node (ref "U5") (pin "10") (pinfunction "COM_10") (pintype "passive"))
      (node (ref "U6") (pin "10") (pinfunction "COM_10") (pintype "passive"))
      (node (ref "U7") (pin "10") (pinfunction "COM_10") (pintype "passive"))
      (node (ref "U8") (pin "10") (pinfunction "COM_10") (pintype "passive"))
    )
    (net (code "58") (name "/a0") (class "Default")
      (node (ref "R31") (pin "1") (pinfunction "1_1") (pintype "passive"))
      (node (ref "R37") (pin "9") (pinfunction "9_9") (pintype "passive"))
      (node (ref "U5") (pin "18") (pinfunction "O1_18") (pintype "passive"))
    )
    (net (code "59") (name "/a1") (class "Default")
      (node (ref "R27") (pin "1") (pinfunction "1_1") (pintype "passive"))
      (node (ref "R37") (pin "8") (pinfunction "8_8") (pintype "passive"))
      (node (ref "U5") (pin "17") (pinfunction "O2_17") (pintype "passive"))
    )
    (net (code "60") (name "/a2") (class "Default")
      (node (ref "R23") (pin "1") (pinfunction "1_1") (pintype "passive"))
      (node (ref "R37") (pin "7") (pinfunction "7_7") (pintype "passive"))
      (node (ref "U5") (pin "16") (pinfunction "O3_16") (pintype "passive"))
    )
    (net (code "61") (name "/a3") (class "Default")
      (node (ref "R19") (pin "1") (pinfunction "1_1") (pintype "passive"))
      (node (ref "R37") (pin "6") (pinfunction "6_6") (pintype "passive"))
      (node (ref "U5") (pin "15") (pinfunction "O4_15") (pintype "passive"))
    )
    (net (code "62") (name "/a4") (class "Default")
      (node (ref "R15") (pin "1") (pinfunction "1_1") (pintype "passive"))
      (node (ref "R37") (pin "5") (pinfunction "5_5") (pintype "passive"))
      (node (ref "U5") (pin "14") (pinfunction "O5_14") (pintype "passive"))
    )
    (net (code "63") (name "/a5") (class "Default")
      (node (ref "R11") (pin "1") (pinfunction "1_1") (pintype "passive"))
      (node (ref "R37") (pin "4") (pinfunction "4_4") (pintype "passive"))
      (node (ref "U5") (pin "13") (pinfunction "O6_13") (pintype "passive"))
    )
    (net (code "64") (name "/a6") (class "Default")
      (node (ref "R37") (pin "3") (pinfunction "3_3") (pintype "passive"))
      (node (ref "R7") (pin "1") (pinfunction "1_1") (pintype "passive"))
      (node (ref "U5") (pin "12") (pinfunction "O7_12") (pintype "passive"))
    )
    (net (code "65") (name "/a7") (class "Default")
      (node (ref "R3") (pin "1") (pinfunction "1_1") (pintype "passive"))
      (node (ref "R37") (pin "2") (pinfunction "2_2") (pintype "passive"))
      (node (ref "U5") (pin "11") (pinfunction "O8_11") (pintype "passive"))
    )
    (net (code "66") (name "/b0") (class "Default")
      (node (ref "R32") (pin "1") (pinfunction "1_1") (pintype "passive"))
      (node (ref "R38") (pin "9") (pinfunction "9_9") (pintype "passive"))
      (node (ref "U6") (pin "18") (pinfunction "O1_18") (pintype "passive"))
    )
    (net (code "67") (name "/b1") (class "Default")
      (node (ref "R28") (pin "1") (pinfunction "1_1") (pintype "passive"))
      (node (ref "R38") (pin "8") (pinfunction "8_8") (pintype "passive"))
      (node (ref "U6") (pin "17") (pinfunction "O2_17") (pintype "passive"))
    )
    (net (code "68") (name "/b2") (class "Default")
      (node (ref "R24") (pin "1") (pinfunction "1_1") (pintype "passive"))
      (node (ref "R38") (pin "7") (pinfunction "7_7") (pintype "passive"))
      (node (ref "U6") (pin "16") (pinfunction "O3_16") (pintype "passive"))
    )
    (net (code "69") (name "/b3") (class "Default")
      (node (ref "R20") (pin "1") (pinfunction "1_1") (pintype "passive"))
      (node (ref "R38") (pin "6") (pinfunction "6_6") (pintype "passive"))
      (node (ref "U6") (pin "15") (pinfunction "O4_15") (pintype "passive"))
    )
    (net (code "70") (name "/b4") (class "Default")
      (node (ref "R16") (pin "1") (pinfunction "1_1") (pintype "passive"))
      (node (ref "R38") (pin "5") (pinfunction "5_5") (pintype "passive"))
      (node (ref "U6") (pin "14") (pinfunction "O5_14") (pintype "passive"))
    )
    (net (code "71") (name "/b5") (class "Default")
      (node (ref "R12") (pin "1") (pinfunction "1_1") (pintype "passive"))
      (node (ref "R38") (pin "4") (pinfunction "4_4") (pintype "passive"))
      (node (ref "U6") (pin "13") (pinfunction "O6_13") (pintype "passive"))
    )
    (net (code "72") (name "/b6") (class "Default")
      (node (ref "R38") (pin "3") (pinfunction "3_3") (pintype "passive"))
      (node (ref "R8") (pin "1") (pinfunction "1_1") (pintype "passive"))
      (node (ref "U6") (pin "12") (pinfunction "O7_12") (pintype "passive"))
    )
    (net (code "73") (name "/b7") (class "Default")
      (node (ref "R38") (pin "2") (pinfunction "2_2") (pintype "passive"))
      (node (ref "R4") (pin "1") (pinfunction "1_1") (pintype "passive"))
      (node (ref "U6") (pin "11") (pinfunction "O8_11") (pintype "passive"))
    )
    (net (code "74") (name "/c0") (class "Default")
      (node (ref "R33") (pin "1") (pinfunction "1_1") (pintype "passive"))
      (node (ref "R39") (pin "9") (pinfunction "9_9") (pintype "passive"))
      (node (ref "U7") (pin "18") (pinfunction "O1_18") (pintype "passive"))
    )
    (net (code "75") (name "/c1") (class "Default")
      (node (ref "R29") (pin "1") (pinfunction "1_1") (pintype "passive"))
      (node (ref "R39") (pin "8") (pinfunction "8_8") (pintype "passive"))
      (node (ref "U7") (pin "17") (pinfunction "O2_17") (pintype "passive"))
    )
    (net (code "76") (name "/c2") (class "Default")
      (node (ref "R25") (pin "1") (pinfunction "1_1") (pintype "passive"))
      (node (ref "R39") (pin "7") (pinfunction "7_7") (pintype "passive"))
      (node (ref "U7") (pin "16") (pinfunction "O3_16") (pintype "passive"))
    )
    (net (code "77") (name "/c3") (class "Default")
      (node (ref "R21") (pin "1") (pinfunction "1_1") (pintype "passive"))
      (node (ref "R39") (pin "6") (pinfunction "6_6") (pintype "passive"))
      (node (ref "U7") (pin "15") (pinfunction "O4_15") (pintype "passive"))
    )
    (net (code "78") (name "/c4") (class "Default")
      (node (ref "R17") (pin "1") (pinfunction "1_1") (pintype "passive"))
      (node (ref "R39") (pin "5") (pinfunction "5_5") (pintype "passive"))
      (node (ref "U7") (pin "14") (pinfunction "O5_14") (pintype "passive"))
    )
    (net (code "79") (name "/c5") (class "Default")
      (node (ref "R13") (pin "1") (pinfunction "1_1") (pintype "passive"))
      (node (ref "R39") (pin "4") (pinfunction "4_4") (pintype "passive"))
      (node (ref "U7") (pin "13") (pinfunction "O6_13") (pintype "passive"))
    )
    (net (code "80") (name "/c6") (class "Default")
      (node (ref "R39") (pin "3") (pinfunction "3_3") (pintype "passive"))
      (node (ref "R9") (pin "1") (pinfunction "1_1") (pintype "passive"))
      (node (ref "U7") (pin "12") (pinfunction "O7_12") (pintype "passive"))
    )
    (net (code "81") (name "/c7") (class "Default")
      (node (ref "R39") (pin "2") (pinfunction "2_2") (pintype "passive"))
      (node (ref "R5") (pin "1") (pinfunction "1_1") (pintype "passive"))
      (node (ref "U7") (pin "11") (pinfunction "O8_11") (pintype "passive"))
    )
    (net (code "82") (name "/d0") (class "Default")
      (node (ref "R34") (pin "1") (pinfunction "1_1") (pintype "passive"))
      (node (ref "R40") (pin "9") (pinfunction "9_9") (pintype "passive"))
      (node (ref "U8") (pin "18") (pinfunction "O1_18") (pintype "passive"))
    )
    (net (code "83") (name "/d1") (class "Default")
      (node (ref "R30") (pin "1") (pinfunction "1_1") (pintype "passive"))
      (node (ref "R40") (pin "8") (pinfunction "8_8") (pintype "passive"))
      (node (ref "U8") (pin "17") (pinfunction "O2_17") (pintype "passive"))
    )
    (net (code "84") (name "/d2") (class "Default")
      (node (ref "R26") (pin "1") (pinfunction "1_1") (pintype "passive"))
      (node (ref "R40") (pin "7") (pinfunction "7_7") (pintype "passive"))
      (node (ref "U8") (pin "16") (pinfunction "O3_16") (pintype "passive"))
    )
    (net (code "85") (name "/d3") (class "Default")
      (node (ref "R22") (pin "1") (pinfunction "1_1") (pintype "passive"))
      (node (ref "R40") (pin "6") (pinfunction "6_6") (pintype "passive"))
      (node (ref "U8") (pin "15") (pinfunction "O4_15") (pintype "passive"))
    )
    (net (code "86") (name "/d4") (class "Default")
      (node (ref "R18") (pin "1") (pinfunction "1_1") (pintype "passive"))
      (node (ref "R40") (pin "5") (pinfunction "5_5") (pintype "passive"))
      (node (ref "U8") (pin "14") (pinfunction "O5_14") (pintype "passive"))
    )
    (net (code "87") (name "/d5") (class "Default")
      (node (ref "R14") (pin "1") (pinfunction "1_1") (pintype "passive"))
      (node (ref "R40") (pin "4") (pinfunction "4_4") (pintype "passive"))
      (node (ref "U8") (pin "13") (pinfunction "O6_13") (pintype "passive"))
    )
    (net (code "88") (name "/d6") (class "Default")
      (node (ref "R10") (pin "1") (pinfunction "1_1") (pintype "passive"))
      (node (ref "R40") (pin "3") (pinfunction "3_3") (pintype "passive"))
      (node (ref "U8") (pin "12") (pinfunction "O7_12") (pintype "passive"))
    )
    (net (code "89") (name "/d7") (class "Default")
      (node (ref "R40") (pin "2") (pinfunction "2_2") (pintype "passive"))
      (node (ref "R6") (pin "1") (pinfunction "1_1") (pintype "passive"))
      (node (ref "U8") (pin "11") (pinfunction "O8_11") (pintype "passive"))
    )
    (net (code "90") (name "3V3") (class "Default")
      (node (ref "C1") (pin "1") (pinfunction "1_1") (pintype "passive"))
      (node (ref "C16") (pin "1") (pinfunction "1_1") (pintype "passive"))
      (node (ref "C17") (pin "1") (pinfunction "1_1") (pintype "passive"))
      (node (ref "C2") (pin "1") (pinfunction "1_1") (pintype "passive"))
      (node (ref "C3") (pin "1") (pinfunction "1_1") (pintype "passive"))
      (node (ref "C4") (pin "1") (pinfunction "1_1") (pintype "passive"))
      (node (ref "C5") (pin "2") (pinfunction "2_2") (pintype "passive"))
      (node (ref "D8") (pin "2") (pinfunction "K_2") (pintype "passive"))
      (node (ref "L2") (pin "2") (pinfunction "2_2") (pintype "passive"))
      (node (ref "R41") (pin "1") (pinfunction "1_1") (pintype "passive"))
      (node (ref "R42") (pin "1") (pinfunction "1_1") (pintype "passive"))
      (node (ref "R43") (pin "1") (pinfunction "1_1") (pintype "passive"))
      (node (ref "R44") (pin "1") (pinfunction "1_1") (pintype "passive"))
      (node (ref "R54") (pin "2") (pinfunction "2_2") (pintype "passive"))
      (node (ref "R55") (pin "2") (pinfunction "2_2") (pintype "passive"))
      (node (ref "R56") (pin "2") (pinfunction "2_2") (pintype "passive"))
      (node (ref "R57") (pin "2") (pinfunction "2_2") (pintype "passive"))
      (node (ref "R60") (pin "2") (pinfunction "2_2") (pintype "passive"))
      (node (ref "R61") (pin "2") (pinfunction "2_2") (pintype "passive"))
      (node (ref "SHT1") (pin "1") (pinfunction "VIN_1") (pintype "passive"))
      (node (ref "U1") (pin "10") (pinfunction "~{CLR}_10") (pintype "passive"))
      (node (ref "U1") (pin "16") (pinfunction "VCC_16") (pintype "passive"))
      (node (ref "U11") (pin "2") (pinfunction "VCC_2") (pintype "passive"))
      (node (ref "U12") (pin "2") (pinfunction "VOUT_2") (pintype "passive"))
      (node (ref "U12") (pin "4") (pinfunction "VO_4") (pintype "passive"))
      (node (ref "U2") (pin "10") (pinfunction "~{CLR}_10") (pintype "passive"))
      (node (ref "U2") (pin "16") (pinfunction "VCC_16") (pintype "passive"))
      (node (ref "U3") (pin "10") (pinfunction "~{CLR}_10") (pintype "passive"))
      (node (ref "U3") (pin "16") (pinfunction "VCC_16") (pintype "passive"))
      (node (ref "U4") (pin "10") (pinfunction "~{CLR}_10") (pintype "passive"))
      (node (ref "U4") (pin "16") (pinfunction "VCC_16") (pintype "passive"))
    )
    (net (code "91") (name "GND") (class "Default")
      (node (ref "5V") (pin "2") (pinfunction "2_2") (pintype "passive"))
      (node (ref "BUTTON 1") (pin "2") (pinfunction "2_2") (pintype "passive"))
      (node (ref "BUTTON 2") (pin "2") (pinfunction "2_2") (pintype "passive"))
      (node (ref "BUTTON 3") (pin "2") (pinfunction "2_2") (pintype "passive"))
      (node (ref "BUTTON 4") (pin "2") (pinfunction "2_2") (pintype "passive"))
      (node (ref "C1") (pin "2") (pinfunction "2_2") (pintype "passive"))
      (node (ref "C10") (pin "2") (pinfunction "2_2") (pintype "passive"))
      (node (ref "C11") (pin "1") (pinfunction "1_1") (pintype "passive"))
      (node (ref "C12") (pin "2") (pinfunction "2_2") (pintype "passive"))
      (node (ref "C13") (pin "2") (pinfunction "2_2") (pintype "passive"))
      (node (ref "C14") (pin "2") (pinfunction "2_2") (pintype "passive"))
      (node (ref "C15") (pin "2") (pinfunction "2_2") (pintype "passive"))
      (node (ref "C16") (pin "2") (pinfunction "2_2") (pintype "passive"))
      (node (ref "C17") (pin "2") (pinfunction "2_2") (pintype "passive"))
      (node (ref "C18") (pin "2") (pinfunction "2_2") (pintype "passive"))
      (node (ref "C19") (pin "2") (pinfunction "2_2") (pintype "passive"))
      (node (ref "C2") (pin "2") (pinfunction "2_2") (pintype "passive"))
      (node (ref "C20") (pin "2") (pinfunction "2_2") (pintype "passive"))
      (node (ref "C21") (pin "2") (pinfunction "2_2") (pintype "passive"))
      (node (ref "C3") (pin "2") (pinfunction "2_2") (pintype "passive"))
      (node (ref "C4") (pin "2") (pinfunction "2_2") (pintype "passive"))
      (node (ref "C5") (pin "1") (pinfunction "1_1") (pintype "passive"))
      (node (ref "C6") (pin "2") (pinfunction "2_2") (pintype "passive"))
      (node (ref "C7") (pin "2") (pinfunction "2_2") (pintype "passive"))
      (node (ref "C8") (pin "2") (pinfunction "2_2") (pintype "passive"))
      (node (ref "C9") (pin "2") (pinfunction "2_2") (pintype "passive"))
      (node (ref "CR1") (pin "2") (pinfunction "GND_2") (pintype "passive"))
      (node (ref "D6") (pin "1") (pinfunction "A_1") (pintype "passive"))
      (node (ref "D8") (pin "1") (pinfunction "A_1") (pintype "passive"))
      (node (ref "HC_1") (pin "2") (pinfunction "GND_2") (pintype "passive"))
      (node (ref "LED3") (pin "2") (pinfunction "K_2") (pintype "passive"))
      (node (ref "LED4") (pin "2") (pinfunction "K_2") (pintype "passive"))
      (node (ref "LOAD") (pin "3") (pinfunction "3_3") (pintype "passive"))
      (node (ref "POWER 9V") (pin "1") (pinfunction "1_1") (pintype "passive"))
      (node (ref "Q1") (pin "2") (pinfunction "E_2") (pintype "passive"))
      (node (ref "Q2") (pin "2") (pinfunction "E_2") (pintype "passive"))
      (node (ref "R36") (pin "1") (pinfunction "1_1") (pintype "passive"))
      (node (ref "R48") (pin "2") (pinfunction "2_2") (pintype "passive"))
      (node (ref "R53") (pin "1") (pinfunction "1_1") (pintype "passive"))
      (node (ref "SHT1") (pin "2") (pinfunction "GND_2") (pintype "passive"))
      (node (ref "SW1") (pin "1") (pinfunction "1_1") (pintype "passive"))
      (node (ref "SW2") (pin "2") (pinfunction "2_2") (pintype "passive"))
      (node (ref "SW2") (pin "3") (pinfunction "1_3") (pintype "passive"))
      (node (ref "SW3") (pin "2") (pinfunction "2_2") (pintype "passive"))
      (node (ref "SW3") (pin "3") (pinfunction "1_3") (pintype "passive"))
      (node (ref "SW4") (pin "2") (pinfunction "2_2") (pintype "passive"))
      (node (ref "SW4") (pin "3") (pinfunction "1_3") (pintype "passive"))
      (node (ref "SW5") (pin "2") (pinfunction "2_2") (pintype "passive"))
      (node (ref "SW5") (pin "3") (pinfunction "1_3") (pintype "passive"))
      (node (ref "U1") (pin "13") (pinfunction "~{OE}_13") (pintype "passive"))
      (node (ref "U1") (pin "8") (pinfunction "GND_8") (pintype "passive"))
      (node (ref "U10") (pin "23") (pinfunction "VSS_1_23") (pintype "power_in"))
      (node (ref "U10") (pin "35") (pinfunction "VSS_2_35") (pintype "power_in"))
      (node (ref "U10") (pin "47") (pinfunction "VSS_3_47") (pintype "power_in"))
      (node (ref "U10") (pin "8") (pinfunction "VSSA_8") (pintype "power_in"))
      (node (ref "U11") (pin "10") (pinfunction "NC_10") (pintype "passive"))
      (node (ref "U11") (pin "11") (pinfunction "NC_11") (pintype "passive"))
      (node (ref "U11") (pin "12") (pinfunction "NC_12") (pintype "passive"))
      (node (ref "U11") (pin "13") (pinfunction "GND_13") (pintype "passive"))
      (node (ref "U11") (pin "5") (pinfunction "NC_5") (pintype "passive"))
      (node (ref "U11") (pin "6") (pinfunction "NC_6") (pintype "passive"))
      (node (ref "U11") (pin "7") (pinfunction "NC_7") (pintype "passive"))
      (node (ref "U11") (pin "8") (pinfunction "NC_8") (pintype "passive"))
      (node (ref "U11") (pin "9") (pinfunction "NC_9") (pintype "passive"))
      (node (ref "U12") (pin "1") (pinfunction "GND_1") (pintype "passive"))
      (node (ref "U2") (pin "13") (pinfunction "~{OE}_13") (pintype "passive"))
      (node (ref "U2") (pin "8") (pinfunction "GND_8") (pintype "passive"))
      (node (ref "U3") (pin "13") (pinfunction "~{OE}_13") (pintype "passive"))
      (node (ref "U3") (pin "8") (pinfunction "GND_8") (pintype "passive"))
      (node (ref "U4") (pin "13") (pinfunction "~{OE}_13") (pintype "passive"))
      (node (ref "U4") (pin "8") (pinfunction "GND_8") (pintype "passive"))
      (node (ref "U5") (pin "9") (pinfunction "GND_9") (pintype "passive"))
      (node (ref "U6") (pin "9") (pinfunction "GND_9") (pintype "passive"))
      (node (ref "U7") (pin "9") (pinfunction "GND_9") (pintype "passive"))
      (node (ref "U8") (pin "9") (pinfunction "GND_9") (pintype "passive"))
      (node (ref "U9") (pin "3") (pinfunction "GND_3") (pintype "passive"))
      (node (ref "U9") (pin "5") (pinfunction "~{ON}/OFF_5") (pintype "passive"))
      (node (ref "U9") (pin "6") (pinfunction "PAD_6") (pintype "passive"))
      (node (ref "USART TEST") (pin "3") (pinfunction "3_3") (pintype "passive"))
    )
    (net (code "92") (name "Net-(BUZZER-Pad2)") (class "Default")
      (node (ref "BUZZER") (pin "2") (pinfunction "2_2") (pintype "passive"))
      (node (ref "R46") (pin "2") (pinfunction "2_2") (pintype "passive"))
    )
    (net (code "93") (name "Net-(C13-Pad1)") (class "Default")
      (node (ref "C13") (pin "1") (pinfunction "1_1") (pintype "passive"))
      (node (ref "R49") (pin "2") (pinfunction "2_2") (pintype "passive"))
      (node (ref "Y1") (pin "1") (pinfunction "1_1") (pintype "passive"))
    )
    (net (code "94") (name "Net-(D1-a)") (class "Default")
      (node (ref "D1") (pin "7") (pinfunction "a_7") (pintype "passive"))
      (node (ref "R3") (pin "2") (pinfunction "2_2") (pintype "passive"))
    )
    (net (code "95") (name "Net-(D1-b)") (class "Default")
      (node (ref "D1") (pin "6") (pinfunction "b_6") (pintype "passive"))
      (node (ref "R7") (pin "2") (pinfunction "2_2") (pintype "passive"))
    )
    (net (code "96") (name "Net-(D1-c)") (class "Default")
      (node (ref "D1") (pin "4") (pinfunction "c_4") (pintype "passive"))
      (node (ref "R11") (pin "2") (pinfunction "2_2") (pintype "passive"))
    )
    (net (code "97") (name "Net-(D1-d)") (class "Default")
      (node (ref "D1") (pin "3") (pinfunction "d_3") (pintype "passive"))
      (node (ref "R15") (pin "2") (pinfunction "2_2") (pintype "passive"))
    )
    (net (code "98") (name "Net-(D1-dp)") (class "Default")
      (node (ref "D1") (pin "5") (pinfunction "dp_5") (pintype "passive"))
      (node (ref "R31") (pin "2") (pinfunction "2_2") (pintype "passive"))
    )
    (net (code "99") (name "Net-(D1-e)") (class "Default")
      (node (ref "D1") (pin "2") (pinfunction "e_2") (pintype "passive"))
      (node (ref "R19") (pin "2") (pinfunction "2_2") (pintype "passive"))
    )
    (net (code "100") (name "Net-(D1-f)") (class "Default")
      (node (ref "D1") (pin "9") (pinfunction "f_9") (pintype "passive"))
      (node (ref "R23") (pin "2") (pinfunction "2_2") (pintype "passive"))
    )
    (net (code "101") (name "Net-(D1-g)") (class "Default")
      (node (ref "D1") (pin "10") (pinfunction "g_10") (pintype "passive"))
      (node (ref "R27") (pin "2") (pinfunction "2_2") (pintype "passive"))
    )
    (net (code "102") (name "Net-(D2-a)") (class "Default")
      (node (ref "D2") (pin "7") (pinfunction "a_7") (pintype "passive"))
      (node (ref "R4") (pin "2") (pinfunction "2_2") (pintype "passive"))
    )
    (net (code "103") (name "Net-(D2-b)") (class "Default")
      (node (ref "D2") (pin "6") (pinfunction "b_6") (pintype "passive"))
      (node (ref "R8") (pin "2") (pinfunction "2_2") (pintype "passive"))
    )
    (net (code "104") (name "Net-(D2-c)") (class "Default")
      (node (ref "D2") (pin "4") (pinfunction "c_4") (pintype "passive"))
      (node (ref "R12") (pin "2") (pinfunction "2_2") (pintype "passive"))
    )
    (net (code "105") (name "Net-(D2-d)") (class "Default")
      (node (ref "D2") (pin "3") (pinfunction "d_3") (pintype "passive"))
      (node (ref "R16") (pin "2") (pinfunction "2_2") (pintype "passive"))
    )
    (net (code "106") (name "Net-(D2-dp)") (class "Default")
      (node (ref "D2") (pin "5") (pinfunction "dp_5") (pintype "passive"))
      (node (ref "R32") (pin "2") (pinfunction "2_2") (pintype "passive"))
    )
    (net (code "107") (name "Net-(D2-e)") (class "Default")
      (node (ref "D2") (pin "2") (pinfunction "e_2") (pintype "passive"))
      (node (ref "R20") (pin "2") (pinfunction "2_2") (pintype "passive"))
    )
    (net (code "108") (name "Net-(D2-f)") (class "Default")
      (node (ref "D2") (pin "9") (pinfunction "f_9") (pintype "passive"))
      (node (ref "R24") (pin "2") (pinfunction "2_2") (pintype "passive"))
    )
    (net (code "109") (name "Net-(D2-g)") (class "Default")
      (node (ref "D2") (pin "10") (pinfunction "g_10") (pintype "passive"))
      (node (ref "R28") (pin "2") (pinfunction "2_2") (pintype "passive"))
    )
    (net (code "110") (name "Net-(D3-a)") (class "Default")
      (node (ref "D3") (pin "7") (pinfunction "a_7") (pintype "passive"))
      (node (ref "R5") (pin "2") (pinfunction "2_2") (pintype "passive"))
    )
    (net (code "111") (name "Net-(D3-b)") (class "Default")
      (node (ref "D3") (pin "6") (pinfunction "b_6") (pintype "passive"))
      (node (ref "R9") (pin "2") (pinfunction "2_2") (pintype "passive"))
    )
    (net (code "112") (name "Net-(D3-c)") (class "Default")
      (node (ref "D3") (pin "4") (pinfunction "c_4") (pintype "passive"))
      (node (ref "R13") (pin "2") (pinfunction "2_2") (pintype "passive"))
    )
    (net (code "113") (name "Net-(D3-d)") (class "Default")
      (node (ref "D3") (pin "3") (pinfunction "d_3") (pintype "passive"))
      (node (ref "R17") (pin "2") (pinfunction "2_2") (pintype "passive"))
    )
    (net (code "114") (name "Net-(D3-dp)") (class "Default")
      (node (ref "D3") (pin "5") (pinfunction "dp_5") (pintype "passive"))
      (node (ref "R33") (pin "2") (pinfunction "2_2") (pintype "passive"))
    )
    (net (code "115") (name "Net-(D3-e)") (class "Default")
      (node (ref "D3") (pin "2") (pinfunction "e_2") (pintype "passive"))
      (node (ref "R21") (pin "2") (pinfunction "2_2") (pintype "passive"))
    )
    (net (code "116") (name "Net-(D3-f)") (class "Default")
      (node (ref "D3") (pin "9") (pinfunction "f_9") (pintype "passive"))
      (node (ref "R25") (pin "2") (pinfunction "2_2") (pintype "passive"))
    )
    (net (code "117") (name "Net-(D3-g)") (class "Default")
      (node (ref "D3") (pin "10") (pinfunction "g_10") (pintype "passive"))
      (node (ref "R29") (pin "2") (pinfunction "2_2") (pintype "passive"))
    )
    (net (code "118") (name "Net-(D4-a)") (class "Default")
      (node (ref "D4") (pin "7") (pinfunction "a_7") (pintype "passive"))
      (node (ref "R6") (pin "2") (pinfunction "2_2") (pintype "passive"))
    )
    (net (code "119") (name "Net-(D4-b)") (class "Default")
      (node (ref "D4") (pin "6") (pinfunction "b_6") (pintype "passive"))
      (node (ref "R10") (pin "2") (pinfunction "2_2") (pintype "passive"))
    )
    (net (code "120") (name "Net-(D4-c)") (class "Default")
      (node (ref "D4") (pin "4") (pinfunction "c_4") (pintype "passive"))
      (node (ref "R14") (pin "2") (pinfunction "2_2") (pintype "passive"))
    )
    (net (code "121") (name "Net-(D4-d)") (class "Default")
      (node (ref "D4") (pin "3") (pinfunction "d_3") (pintype "passive"))
      (node (ref "R18") (pin "2") (pinfunction "2_2") (pintype "passive"))
    )
    (net (code "122") (name "Net-(D4-dp)") (class "Default")
      (node (ref "D4") (pin "5") (pinfunction "dp_5") (pintype "passive"))
      (node (ref "R34") (pin "2") (pinfunction "2_2") (pintype "passive"))
    )
    (net (code "123") (name "Net-(D4-e)") (class "Default")
      (node (ref "D4") (pin "2") (pinfunction "e_2") (pintype "passive"))
      (node (ref "R22") (pin "2") (pinfunction "2_2") (pintype "passive"))
    )
    (net (code "124") (name "Net-(D4-f)") (class "Default")
      (node (ref "D4") (pin "9") (pinfunction "f_9") (pintype "passive"))
      (node (ref "R26") (pin "2") (pinfunction "2_2") (pintype "passive"))
    )
    (net (code "125") (name "Net-(D4-g)") (class "Default")
      (node (ref "D4") (pin "10") (pinfunction "g_10") (pintype "passive"))
      (node (ref "R30") (pin "2") (pinfunction "2_2") (pintype "passive"))
    )
    (net (code "126") (name "Net-(D6-K)") (class "Default")
      (node (ref "D6") (pin "2") (pinfunction "K_2") (pintype "passive"))
      (node (ref "L1") (pin "1") (pinfunction "1_1") (pintype "passive"))
      (node (ref "U9") (pin "2") (pinfunction "OUT_2") (pintype "passive"))
    )
    (net (code "127") (name "Net-(D7-K)") (class "Default")
      (node (ref "C15") (pin "1") (pinfunction "1_1") (pintype "passive"))
      (node (ref "D7") (pin "2") (pinfunction "K_2") (pintype "passive"))
      (node (ref "U12") (pin "3") (pinfunction "VIN_3") (pintype "power_in"))
    )
    (net (code "128") (name "Net-(HC_1-RX)") (class "Default")
      (node (ref "HC_1") (pin "3") (pinfunction "RX_3") (pintype "passive"))
      (node (ref "R52") (pin "1") (pinfunction "1_1") (pintype "passive"))
    )
    (net (code "129") (name "Net-(HC_1-SET)") (class "Default")
      (node (ref "HC_1") (pin "5") (pinfunction "SET_5") (pintype "passive"))
      (node (ref "R50") (pin "1") (pinfunction "1_1") (pintype "passive"))
    )
    (net (code "130") (name "Net-(HC_1-TX)") (class "Default")
      (node (ref "HC_1") (pin "4") (pinfunction "TX_4") (pintype "passive"))
      (node (ref "R51") (pin "1") (pinfunction "1_1") (pintype "passive"))
    )
    (net (code "131") (name "Net-(LED1-A)") (class "Default")
      (node (ref "LED1") (pin "1") (pinfunction "A_1") (pintype "passive"))
      (node (ref "R1") (pin "2") (pinfunction "2_2") (pintype "passive"))
    )
    (net (code "132") (name "Net-(LED1-K)") (class "Default")
      (node (ref "LED1") (pin "2") (pinfunction "K_2") (pintype "passive"))
      (node (ref "LED2") (pin "2") (pinfunction "K_2") (pintype "passive"))
      (node (ref "Q1") (pin "3") (pinfunction "C_3") (pintype "passive"))
    )
    (net (code "133") (name "Net-(LED2-A)") (class "Default")
      (node (ref "LED2") (pin "1") (pinfunction "A_1") (pintype "passive"))
      (node (ref "R2") (pin "2") (pinfunction "2_2") (pintype "passive"))
    )
    (net (code "134") (name "Net-(LED3-A)") (class "Default")
      (node (ref "LED3") (pin "1") (pinfunction "A_1") (pintype "passive"))
      (node (ref "R45") (pin "1") (pinfunction "1_1") (pintype "passive"))
    )
    (net (code "135") (name "Net-(LED4-A)") (class "Default")
      (node (ref "LED4") (pin "1") (pinfunction "A_1") (pintype "passive"))
      (node (ref "R54") (pin "1") (pinfunction "1_1") (pintype "passive"))
    )
    (net (code "136") (name "Net-(LED5-A)") (class "Default")
      (node (ref "LED5") (pin "1") (pinfunction "A_1") (pintype "passive"))
      (node (ref "R55") (pin "1") (pinfunction "1_1") (pintype "passive"))
    )
    (net (code "137") (name "Net-(Q1-B)") (class "Default")
      (node (ref "Q1") (pin "1") (pinfunction "B_1") (pintype "passive"))
      (node (ref "R35") (pin "2") (pinfunction "2_2") (pintype "passive"))
      (node (ref "R36") (pin "2") (pinfunction "2_2") (pintype "passive"))
    )
    (net (code "138") (name "Net-(Q2-B)") (class "Default")
      (node (ref "Q2") (pin "1") (pinfunction "B_1") (pintype "passive"))
      (node (ref "R47") (pin "1") (pinfunction "1_1") (pintype "passive"))
      (node (ref "R48") (pin "1") (pinfunction "1_1") (pintype "passive"))
    )
    (net (code "139") (name "Net-(Q2-C)") (class "Default")
      (node (ref "Q2") (pin "3") (pinfunction "C_3") (pintype "passive"))
      (node (ref "R46") (pin "1") (pinfunction "1_1") (pintype "passive"))
    )
    (net (code "140") (name "Net-(U1-SDO)") (class "Default")
      (node (ref "U1") (pin "9") (pinfunction "SDO_9") (pintype "passive"))
      (node (ref "U2") (pin "14") (pinfunction "SDI_14") (pintype "passive"))
    )
    (net (code "141") (name "Net-(U2-SDO)") (class "Default")
      (node (ref "U2") (pin "9") (pinfunction "SDO_9") (pintype "passive"))
      (node (ref "U3") (pin "14") (pinfunction "SDI_14") (pintype "passive"))
    )
    (net (code "142") (name "Net-(U3-SDO)") (class "Default")
      (node (ref "U3") (pin "9") (pinfunction "SDO_9") (pintype "passive"))
      (node (ref "U4") (pin "14") (pinfunction "SDI_14") (pintype "passive"))
    )
    (net (code "143") (name "Net-(U10-BOOT0)") (class "Default")
      (node (ref "R53") (pin "2") (pinfunction "2_2") (pintype "passive"))
      (node (ref "U10") (pin "44") (pinfunction "BOOT0_44") (pintype "input"))
    )
    (net (code "144") (name "Net-(U10-NRST)") (class "Default")
      (node (ref "C14") (pin "1") (pinfunction "1_1") (pintype "passive"))
      (node (ref "SW1") (pin "2") (pinfunction "2_2") (pintype "passive"))
      (node (ref "U10") (pin "7") (pinfunction "NRST_7") (pintype "bidirectional"))
    )
    (net (code "145") (name "Net-(U10-OSC_IN_¦_PD0)") (class "Default")
      (node (ref "C12") (pin "1") (pinfunction "1_1") (pintype "passive"))
      (node (ref "U10") (pin "5") (pinfunction "OSC_IN_¦_PD0_5") (pintype "input"))
      (node (ref "Y1") (pin "2") (pinfunction "2_2") (pintype "passive"))
    )
    (net (code "146") (name "Net-(U10-OSC_OUT_¦_PD1)") (class "Default")
      (node (ref "R49") (pin "1") (pinfunction "1_1") (pintype "passive"))
      (node (ref "U10") (pin "6") (pinfunction "OSC_OUT_¦_PD1_6") (pintype "output"))
    )
    (net (code "147") (name "Net-(U11-32KHz)") (class "Default")
      (node (ref "R42") (pin "2") (pinfunction "2_2") (pintype "passive"))
      (node (ref "U11") (pin "1") (pinfunction "32KHz_1") (pintype "passive"))
    )
    (net (code "148") (name "VBAT") (class "Default")
      (node (ref "C10") (pin "1") (pinfunction "1_1") (pintype "passive"))
      (node (ref "CR1") (pin "1") (pinfunction "VCC_1") (pintype "passive"))
      (node (ref "U10") (pin "1") (pinfunction "VBAT_1") (pintype "power_in"))
      (node (ref "U11") (pin "14") (pinfunction "VBAT_14") (pintype "passive"))
    )
    (net (code "149") (name "VCC") (class "Default")
      (node (ref "5V") (pin "1") (pinfunction "1_1") (pintype "passive"))
      (node (ref "BUZZER") (pin "1") (pinfunction "1_1") (pintype "passive"))
      (node (ref "C11") (pin "2") (pinfunction "2_2") (pintype "passive"))
      (node (ref "C8") (pin "1") (pinfunction "1_1") (pintype "passive"))
      (node (ref "C9") (pin "1") (pinfunction "1_1") (pintype "passive"))
      (node (ref "D7") (pin "1") (pinfunction "A_1") (pintype "passive"))
      (node (ref "HC_1") (pin "1") (pinfunction "VCC_1") (pintype "passive"))
      (node (ref "L1") (pin "2") (pinfunction "2_2") (pintype "passive"))
      (node (ref "L4") (pin "2") (pinfunction "2_2") (pintype "passive"))
      (node (ref "R1") (pin "1") (pinfunction "1_1") (pintype "passive"))
      (node (ref "R2") (pin "1") (pinfunction "1_1") (pintype "passive"))
      (node (ref "R45") (pin "2") (pinfunction "2_2") (pintype "passive"))
      (node (ref "U9") (pin "4") (pinfunction "FB_4") (pintype "passive"))
      (node (ref "USART TEST") (pin "4") (pinfunction "4_4") (pintype "passive"))
    )
    (net (code "150") (name "VDD") (class "Default")
      (node (ref "C18") (pin "1") (pinfunction "1_1") (pintype "passive"))
      (node (ref "C19") (pin "1") (pinfunction "1_1") (pintype "passive"))
      (node (ref "C20") (pin "1") (pinfunction "1_1") (pintype "passive"))
      (node (ref "C21") (pin "1") (pinfunction "1_1") (pintype "passive"))
      (node (ref "L2") (pin "1") (pinfunction "1_1") (pintype "passive"))
      (node (ref "U10") (pin "24") (pinfunction "VDD_1_24") (pintype "power_in"))
      (node (ref "U10") (pin "36") (pinfunction "VDD_2_36") (pintype "power_in"))
      (node (ref "U10") (pin "48") (pinfunction "VDD_3_48") (pintype "power_in"))
      (node (ref "U10") (pin "9") (pinfunction "VDDA_9") (pintype "power_in"))
    )
    (net (code "151") (name "VIN") (class "Default")
      (node (ref "C6") (pin "1") (pinfunction "1_1") (pintype "passive"))
      (node (ref "C7") (pin "1") (pinfunction "1_1") (pintype "passive"))
      (node (ref "D5") (pin "2") (pinfunction "K_2") (pintype "passive"))
      (node (ref "L3") (pin "2") (pinfunction "2_2") (pintype "passive"))
      (node (ref "U9") (pin "1") (pinfunction "VIN_1") (pintype "passive"))
    )
    (net (code "152") (name "unconnected-(Hole1-Screw-Pad1)") (class "Default")
      (node (ref "Hole1") (pin "1") (pinfunction "Screw_1") (pintype "passive+no_connect"))
    )
    (net (code "153") (name "unconnected-(Hole2-Screw-Pad1)") (class "Default")
      (node (ref "Hole2") (pin "1") (pinfunction "Screw_1") (pintype "passive+no_connect"))
    )
    (net (code "154") (name "unconnected-(Hole3-Screw-Pad1)") (class "Default")
      (node (ref "Hole3") (pin "1") (pinfunction "Screw_1") (pintype "passive+no_connect"))
    )
    (net (code "155") (name "unconnected-(Hole4-Screw-Pad1)") (class "Default")
      (node (ref "Hole4") (pin "1") (pinfunction "Screw_1") (pintype "passive+no_connect"))
    )
    (net (code "156") (name "unconnected-(U4-SDO-Pad9)") (class "Default")
      (node (ref "U4") (pin "9") (pinfunction "SDO_9") (pintype "passive+no_connect"))
    )
    (net (code "157") (name "unconnected-(U9-GND-Pad6)") (class "Default")
      (node (ref "U9") (pin "6") (pinfunction "GND_6") (pintype "passive"))
    )
    (net (code "158") (name "unconnected-(U10-JNTRST_¦_TIM3_CH1{slash}PB4{slash}SPI1_MISO-Pad40)") (class "Default")
      (node (ref "U10") (pin "40") (pinfunction "JNTRST_¦_TIM3_CH1/PB4/SPI1_MISO_40") (pintype "bidirectional"))
    )
    (net (code "159") (name "unconnected-(U10-JTDO_¦_TIM2_CH2{slash}PB3{slash}TRACESWO{slash}SPI1_SCK-Pad39)") (class "Default")
      (node (ref "U10") (pin "39") (pinfunction "JTDO_¦_TIM2_CH2/PB3/TRACESWO/SPI1_SCK_39") (pintype "bidirectional"))
    )
    (net (code "160") (name "unconnected-(U10-PA4{slash}SPI1_NSS{slash}USART2_CK{slash}ADC12_IN4-Pad14)") (class "Default")
      (node (ref "U10") (pin "14") (pinfunction "PA4/SPI1_NSS/USART2_CK/ADC12_IN4_14") (pintype "bidirectional"))
    )
    (net (code "161") (name "unconnected-(U10-PA5{slash}SPI1_SCK{slash}ADC12_IN5-Pad15)") (class "Default")
      (node (ref "U10") (pin "15") (pinfunction "PA5/SPI1_SCK/ADC12_IN5_15") (pintype "bidirectional"))
    )
    (net (code "162") (name "unconnected-(U10-PA6{slash}SPI1_MISO{slash}ADC12_IN6{slash}TIM3_CH1_¦_TIM1_BKIN-Pad16)") (class "Default")
      (node (ref "U10") (pin "16") (pinfunction "PA6/SPI1_MISO/ADC12_IN6/TIM3_CH1_¦_TIM1_BKIN_16") (pintype "bidirectional"))
    )
    (net (code "163") (name "unconnected-(U10-PA7{slash}SPI1_MOSI{slash}ADC12_IN7{slash}TIM3_CH2_¦_TIM1_CH1N-Pad17)") (class "Default")
      (node (ref "U10") (pin "17") (pinfunction "PA7/SPI1_MOSI/ADC12_IN7/TIM3_CH2_¦_TIM1_CH1N_17") (pintype "bidirectional"))
    )
    (net (code "164") (name "unconnected-(U10-PA8{slash}USART1_CK{slash}TIM1_CH1{slash}MCO-Pad29)") (class "Default")
      (node (ref "U10") (pin "29") (pinfunction "PA8/USART1_CK/TIM1_CH1/MCO_29") (pintype "bidirectional"))
    )
    (net (code "165") (name "unconnected-(U10-PA11{slash}USART1_CTS{slash}CANRX{slash}USBDM{slash}TIM1_CH4-Pad32)") (class "Default")
      (node (ref "U10") (pin "32") (pinfunction "PA11/USART1_CTS/CANRX/USBDM/TIM1_CH4_32") (pintype "bidirectional"))
    )
    (net (code "166") (name "unconnected-(U10-PA12{slash}USART1_RTS{slash}CANTX{slash}USBDP{slash}TIM1_ETR-Pad33)") (class "Default")
      (node (ref "U10") (pin "33") (pinfunction "PA12/USART1_RTS/CANTX/USBDP/TIM1_ETR_33") (pintype "bidirectional"))
    )
    (net (code "167") (name "unconnected-(U10-PB1{slash}ADC12_IN9{slash}TIM3_CH4_¦_TIM1_CH3N-Pad19)") (class "Default")
      (node (ref "U10") (pin "19") (pinfunction "PB1/ADC12_IN9/TIM3_CH4_¦_TIM1_CH3N_19") (pintype "bidirectional"))
    )
    (net (code "168") (name "unconnected-(U10-PB2{slash}BOOT1-Pad20)") (class "Default")
      (node (ref "U10") (pin "20") (pinfunction "PB2/BOOT1_20") (pintype "bidirectional"))
    )
    (net (code "169") (name "unconnected-(U10-PC13{slash}TAMPER-RTC-Pad2)") (class "Default")
      (node (ref "U10") (pin "2") (pinfunction "PC13/TAMPER-RTC_2") (pintype "bidirectional"))
    )
    (net (code "170") (name "unconnected-(U10-PC14{slash}OSC32_IN-Pad3)") (class "Default")
      (node (ref "U10") (pin "3") (pinfunction "PC14/OSC32_IN_3") (pintype "bidirectional+no_connect"))
    )
    (net (code "171") (name "unconnected-(U10-PC15{slash}OSC32_OUT-Pad4)") (class "Default")
      (node (ref "U10") (pin "4") (pinfunction "PC15/OSC32_OUT_4") (pintype "bidirectional+no_connect"))
    )
    (net (code "172") (name "unconnected-(U11-~{RST}-Pad4)") (class "Default")
      (node (ref "U11") (pin "4") (pinfunction "~{RST}_4") (pintype "passive+no_connect"))
    )
  )
)
